# Uav_V2.net
KiCad netlist of a schematic drawn in Altium Designer
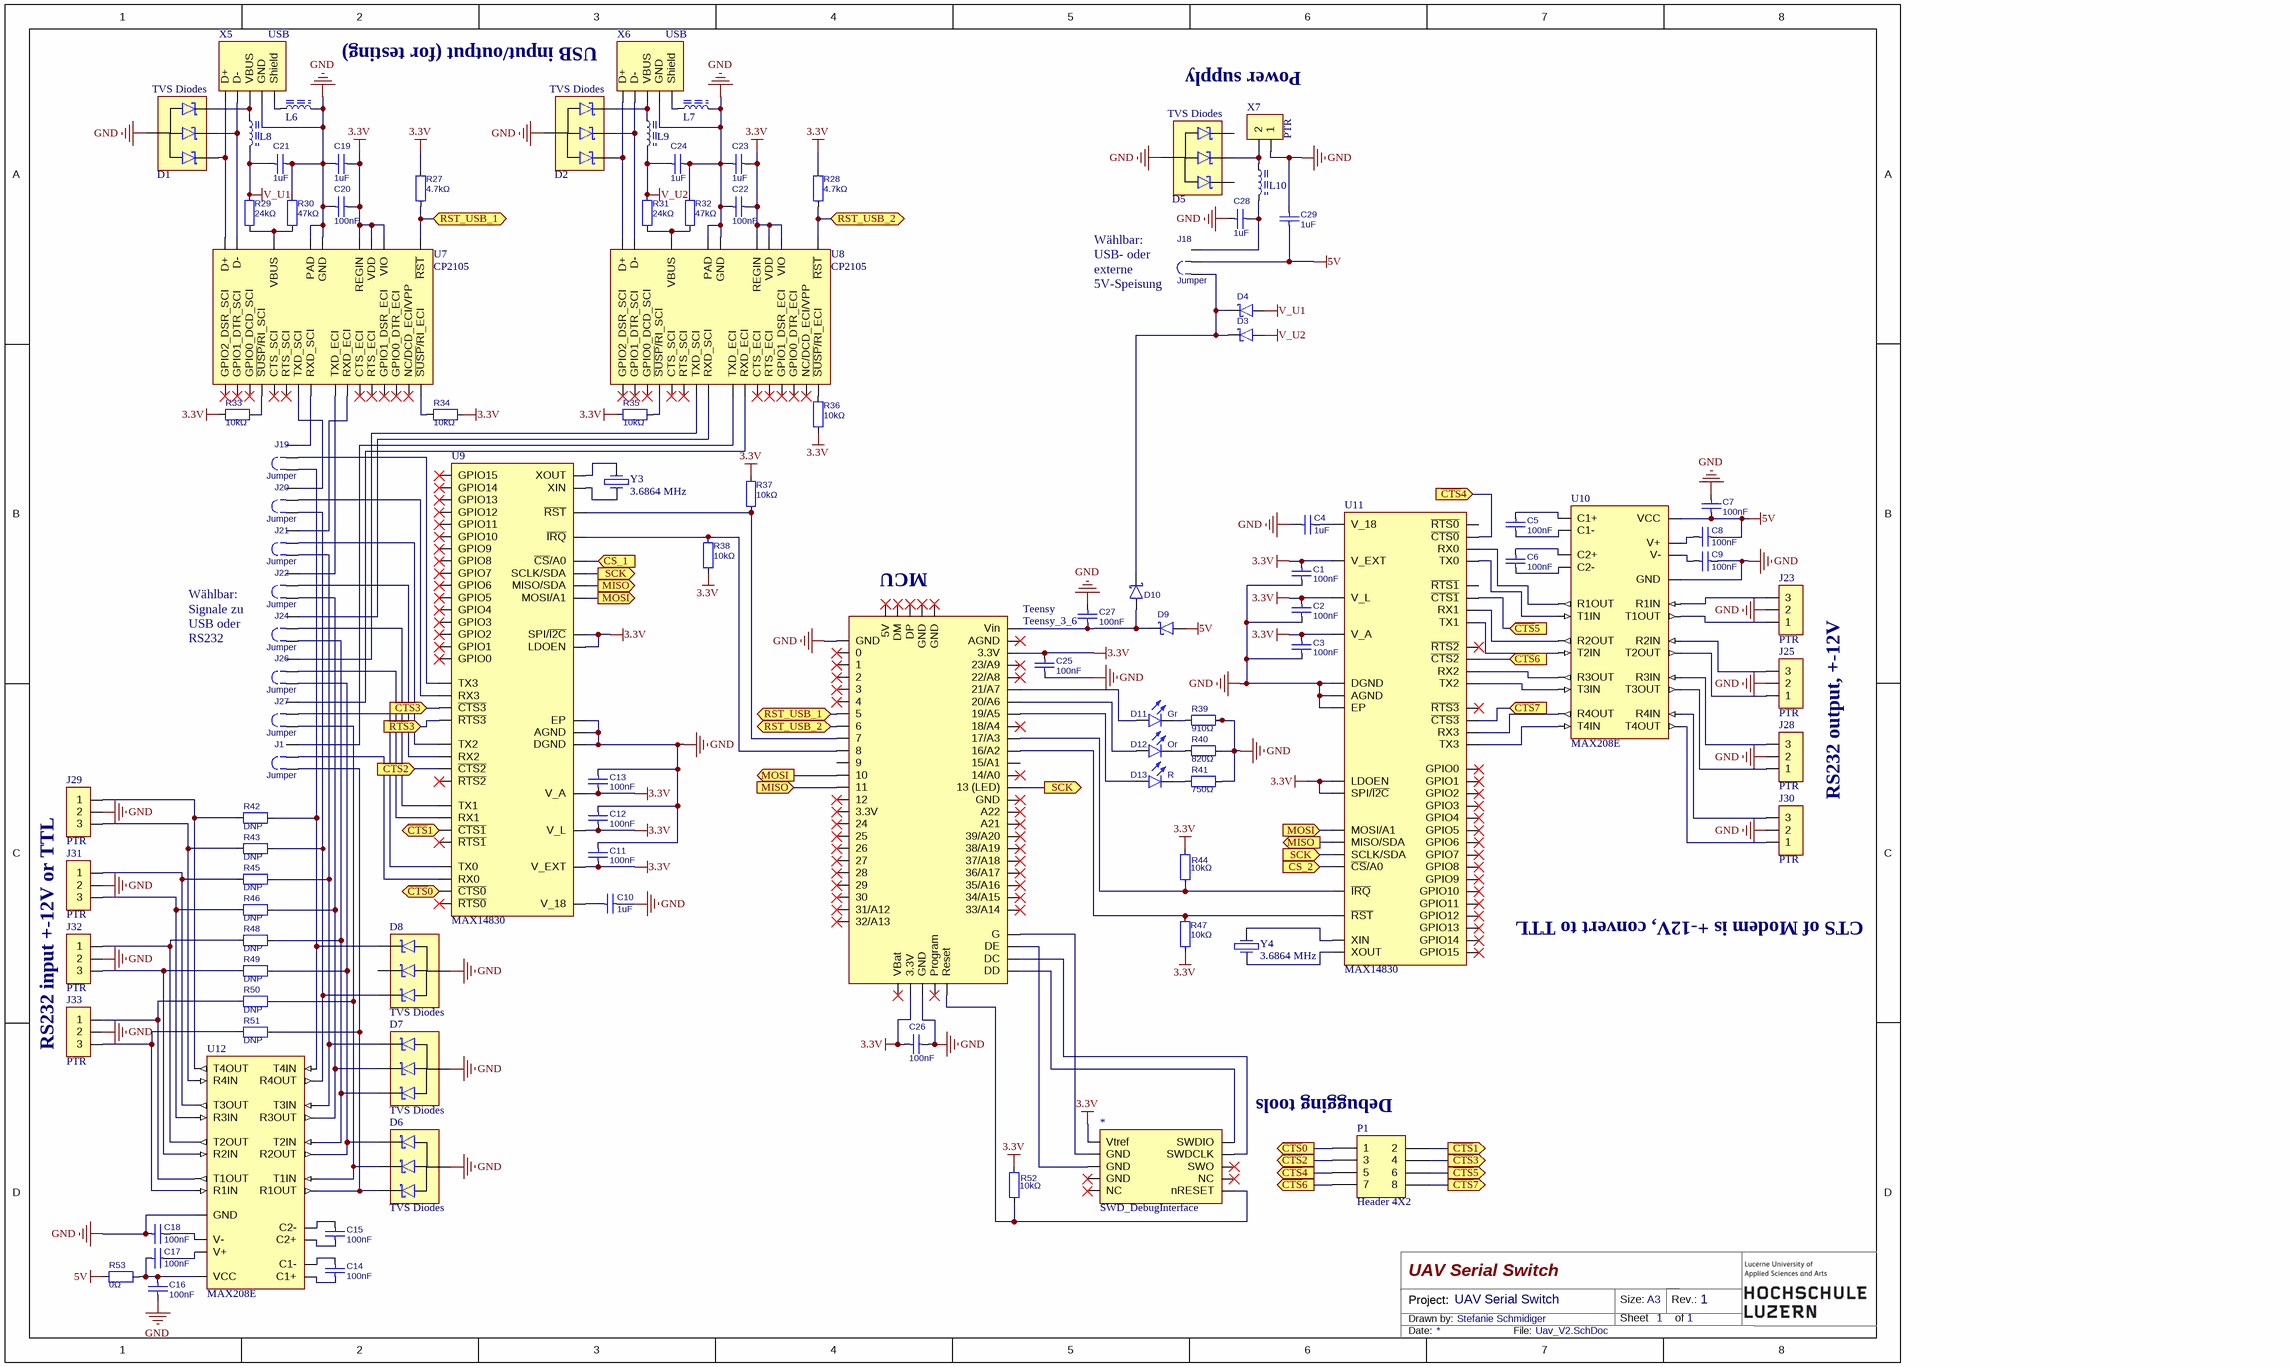
[diagram p0: Uav_V2.SchDoc]

(export (version "E")
  (design (tool "Eeschema 10.0.6"))
  (components
    (comp (ref "*")
      (value "SWD_DebugInterface")
      (footprint "SWD Debug Interface")
      (libsource (lib "UAV") (part "SWD_DebugInterface"))
    )
    (comp (ref "C1")
      (value "100nF")
      (footprint "0603")
      (description "Keramikkondensator 0603")
      (fields (field (name "CHANGED BY") "taalbiss"))
      (libsource (lib "CCE_Database_Libs") (part "C_Normal"))
    )
    (comp (ref "C2")
      (value "100nF")
      (footprint "0603")
      (description "Keramikkondensator 0603")
      (fields (field (name "CHANGED BY") "taalbiss"))
      (libsource (lib "CCE_Database_Libs") (part "C_Normal"))
    )
    (comp (ref "C3")
      (value "100nF")
      (footprint "0603")
      (description "Keramikkondensator 0603")
      (fields (field (name "CHANGED BY") "taalbiss"))
      (libsource (lib "CCE_Database_Libs") (part "C_Normal"))
    )
    (comp (ref "C4")
      (value "1uF")
      (footprint "0603")
      (description "Keramikkondensator 0603")
      (fields (field (name "CHANGED BY") "taalbiss"))
      (libsource (lib "CCE_Database_Libs") (part "C_Normal"))
    )
    (comp (ref "C5")
      (value "100nF")
      (footprint "0603")
      (description "Keramikkondensator 0603")
      (fields (field (name "CHANGED BY") "taalbiss"))
      (libsource (lib "CCE_Database_Libs") (part "C_Normal"))
    )
    (comp (ref "C6")
      (value "100nF")
      (footprint "0603")
      (description "Keramikkondensator 0603")
      (fields (field (name "CHANGED BY") "taalbiss"))
      (libsource (lib "CCE_Database_Libs") (part "C_Normal"))
    )
    (comp (ref "C7")
      (value "100nF")
      (footprint "0603")
      (description "Keramikkondensator 0603")
      (fields (field (name "CHANGED BY") "taalbiss"))
      (libsource (lib "CCE_Database_Libs") (part "C_Normal"))
    )
    (comp (ref "C8")
      (value "100nF")
      (footprint "0603")
      (description "Keramikkondensator 0603")
      (fields (field (name "CHANGED BY") "taalbiss"))
      (libsource (lib "CCE_Database_Libs") (part "C_Normal"))
    )
    (comp (ref "C9")
      (value "100nF")
      (footprint "0603")
      (description "Keramikkondensator 0603")
      (fields (field (name "CHANGED BY") "taalbiss"))
      (libsource (lib "CCE_Database_Libs") (part "C_Normal"))
    )
    (comp (ref "C10")
      (value "1uF")
      (footprint "0603")
      (description "Keramikkondensator 0603")
      (fields (field (name "CHANGED BY") "taalbiss"))
      (libsource (lib "CCE_Database_Libs") (part "C_Normal"))
    )
    (comp (ref "C11")
      (value "100nF")
      (footprint "0603")
      (description "Keramikkondensator 0603")
      (fields (field (name "CHANGED BY") "taalbiss"))
      (libsource (lib "CCE_Database_Libs") (part "C_Normal"))
    )
    (comp (ref "C12")
      (value "100nF")
      (footprint "0603")
      (description "Keramikkondensator 0603")
      (fields (field (name "CHANGED BY") "taalbiss"))
      (libsource (lib "CCE_Database_Libs") (part "C_Normal"))
    )
    (comp (ref "C13")
      (value "100nF")
      (footprint "0603")
      (description "Keramikkondensator 0603")
      (fields (field (name "CHANGED BY") "taalbiss"))
      (libsource (lib "CCE_Database_Libs") (part "C_Normal"))
    )
    (comp (ref "C14")
      (value "100nF")
      (footprint "0603")
      (description "Keramikkondensator 0603")
      (fields (field (name "CHANGED BY") "taalbiss"))
      (libsource (lib "CCE_Database_Libs") (part "C_Normal"))
    )
    (comp (ref "C15")
      (value "100nF")
      (footprint "0603")
      (description "Keramikkondensator 0603")
      (fields (field (name "CHANGED BY") "taalbiss"))
      (libsource (lib "CCE_Database_Libs") (part "C_Normal"))
    )
    (comp (ref "C16")
      (value "100nF")
      (footprint "0603")
      (description "Keramikkondensator 0603")
      (fields (field (name "CHANGED BY") "taalbiss"))
      (libsource (lib "CCE_Database_Libs") (part "C_Normal"))
    )
    (comp (ref "C17")
      (value "100nF")
      (footprint "0603")
      (description "Keramikkondensator 0603")
      (fields (field (name "CHANGED BY") "taalbiss"))
      (libsource (lib "CCE_Database_Libs") (part "C_Normal"))
    )
    (comp (ref "C18")
      (value "100nF")
      (footprint "0603")
      (description "Keramikkondensator 0603")
      (fields (field (name "CHANGED BY") "taalbiss"))
      (libsource (lib "CCE_Database_Libs") (part "C_Normal"))
    )
    (comp (ref "C19")
      (value "1uF")
      (footprint "0603")
      (description "Keramikkondensator 0603")
      (fields (field (name "CHANGED BY") "taalbiss"))
      (libsource (lib "CCE_Database_Libs") (part "C_Normal"))
    )
    (comp (ref "C20")
      (value "100nF")
      (footprint "0603")
      (description "Keramikkondensator 0603")
      (fields (field (name "CHANGED BY") "taalbiss"))
      (libsource (lib "CCE_Database_Libs") (part "C_Normal"))
    )
    (comp (ref "C21")
      (value "1uF")
      (footprint "0603")
      (description "Keramikkondensator 0603")
      (fields (field (name "CHANGED BY") "taalbiss"))
      (libsource (lib "CCE_Database_Libs") (part "C_Normal"))
    )
    (comp (ref "C22")
      (value "100nF")
      (footprint "0603")
      (description "Keramikkondensator 0603")
      (fields (field (name "CHANGED BY") "taalbiss"))
      (libsource (lib "CCE_Database_Libs") (part "C_Normal"))
    )
    (comp (ref "C23")
      (value "1uF")
      (footprint "0603")
      (description "Keramikkondensator 0603")
      (fields (field (name "CHANGED BY") "taalbiss"))
      (libsource (lib "CCE_Database_Libs") (part "C_Normal"))
    )
    (comp (ref "C24")
      (value "1uF")
      (footprint "0603")
      (description "Keramikkondensator 0603")
      (fields (field (name "CHANGED BY") "taalbiss"))
      (libsource (lib "CCE_Database_Libs") (part "C_Normal"))
    )
    (comp (ref "C25")
      (value "100nF")
      (footprint "0603")
      (description "Keramikkondensator 0603")
      (fields (field (name "CHANGED BY") "taalbiss"))
      (libsource (lib "CCE_Database_Libs") (part "C_Normal"))
    )
    (comp (ref "C26")
      (value "100nF")
      (footprint "0603")
      (description "Keramikkondensator 0603")
      (fields (field (name "CHANGED BY") "taalbiss"))
      (libsource (lib "CCE_Database_Libs") (part "C_Normal"))
    )
    (comp (ref "C27")
      (value "100nF")
      (footprint "0603")
      (description "Keramikkondensator 0603")
      (fields (field (name "CHANGED BY") "taalbiss"))
      (libsource (lib "CCE_Database_Libs") (part "C_Normal"))
    )
    (comp (ref "C28")
      (value "1uF")
      (footprint "0603")
      (description "Keramikkondensator 0603")
      (fields (field (name "CHANGED BY") "taalbiss"))
      (libsource (lib "CCE_Database_Libs") (part "C_Normal"))
    )
    (comp (ref "C29")
      (value "1uF")
      (footprint "0603")
      (description "Keramikkondensator 0603")
      (fields (field (name "CHANGED BY") "taalbiss"))
      (libsource (lib "CCE_Database_Libs") (part "C_Normal"))
    )
    (comp (ref "D1")
      (value "TVS Diodes")
      (footprint "UAV:SOT-143-4")
      (libsource (lib "UAV") (part "TVS_Diode_3fach"))
    )
    (comp (ref "D2")
      (value "TVS Diodes")
      (footprint "UAV:SOT-143-4")
      (libsource (lib "UAV") (part "TVS_Diode_3fach"))
    )
    (comp (ref "D3")
      (value "?")
      (footprint "SOD_123")
      (description "Schottky Diode SOD-123")
      (fields (field (name "CHANGED BY") "taalbiss"))
      (libsource (lib "CCE_Database_Libs") (part "Diode_Schottky"))
    )
    (comp (ref "D4")
      (value "?")
      (footprint "SOD_123")
      (description "Schottky Diode SOD-123")
      (fields (field (name "CHANGED BY") "taalbiss"))
      (libsource (lib "CCE_Database_Libs") (part "Diode_Schottky"))
    )
    (comp (ref "D5")
      (value "TVS Diodes")
      (footprint "UAV:SOT-143-4")
      (libsource (lib "UAV") (part "TVS_Diode_3fach"))
    )
    (comp (ref "D6")
      (value "TVS Diodes")
      (footprint "UAV:SOT-143-4")
      (libsource (lib "") (part "TVS_Diode_3fach_1"))
    )
    (comp (ref "D7")
      (value "TVS Diodes")
      (footprint "UAV:SOT-143-4")
      (libsource (lib "") (part "TVS_Diode_3fach_1"))
    )
    (comp (ref "D8")
      (value "TVS Diodes")
      (footprint "UAV:SOT-143-4")
      (libsource (lib "") (part "TVS_Diode_3fach_1"))
    )
    (comp (ref "D9")
      (value "?")
      (footprint "SOD_123")
      (description "Schottky Diode SOD-123")
      (fields (field (name "CHANGED BY") "taalbiss"))
      (libsource (lib "CCE_Database_Libs") (part "Diode_Schottky"))
    )
    (comp (ref "D10")
      (value "?")
      (footprint "SOD_123")
      (description "Schottky Diode SOD-123")
      (fields (field (name "CHANGED BY") "taalbiss"))
      (libsource (lib "CCE_Database_Libs") (part "Diode_Schottky"))
    )
    (comp (ref "D11")
      (value "Gr")
      (footprint "0603D")
      (description "LED SMD 0603")
      (fields (field (name "CHANGED BY") "taalbiss"))
      (libsource (lib "CCE_Database_Libs") (part "LED"))
    )
    (comp (ref "D12")
      (value "Or")
      (footprint "0603D")
      (description "LED SMD 0603")
      (fields (field (name "CHANGED BY") "taalbiss"))
      (libsource (lib "CCE_Database_Libs") (part "LED"))
    )
    (comp (ref "D13")
      (value "R")
      (footprint "0603D")
      (description "LED SMD 0603")
      (fields (field (name "CHANGED BY") "taalbiss"))
      (libsource (lib "CCE_Database_Libs") (part "LED"))
    )
    (comp (ref "J1")
      (value "Jumper")
      (footprint "HDR1X3")
      (description "Jumper THT 2.54mm 1x3")
      (fields (field (name "CHANGED BY") "taalbiss"))
      (libsource (lib "CCE_Database_Libs") (part "Jumper_1x3"))
    )
    (comp (ref "J18")
      (value "Jumper")
      (footprint "HDR1X3")
      (description "Jumper THT 2.54mm 1x3")
      (fields (field (name "CHANGED BY") "taalbiss"))
      (libsource (lib "CCE_Database_Libs") (part "Jumper_1x3"))
    )
    (comp (ref "J19")
      (value "Jumper")
      (footprint "HDR1X3")
      (description "Jumper THT 2.54mm 1x3")
      (fields (field (name "CHANGED BY") "taalbiss"))
      (libsource (lib "CCE_Database_Libs") (part "Jumper_1x3"))
    )
    (comp (ref "J20")
      (value "Jumper")
      (footprint "HDR1X3")
      (description "Jumper THT 2.54mm 1x3")
      (fields (field (name "CHANGED BY") "taalbiss"))
      (libsource (lib "CCE_Database_Libs") (part "Jumper_1x3"))
    )
    (comp (ref "J21")
      (value "Jumper")
      (footprint "HDR1X3")
      (description "Jumper THT 2.54mm 1x3")
      (fields (field (name "CHANGED BY") "taalbiss"))
      (libsource (lib "CCE_Database_Libs") (part "Jumper_1x3"))
    )
    (comp (ref "J22")
      (value "Jumper")
      (footprint "HDR1X3")
      (description "Jumper THT 2.54mm 1x3")
      (fields (field (name "CHANGED BY") "taalbiss"))
      (libsource (lib "CCE_Database_Libs") (part "Jumper_1x3"))
    )
    (comp (ref "J23") (value "PTR") (footprint "PTR_1X3") (libsource (lib "") (part "Header_1x3_1")))
    (comp (ref "J24")
      (value "Jumper")
      (footprint "HDR1X3")
      (description "Jumper THT 2.54mm 1x3")
      (fields (field (name "CHANGED BY") "taalbiss"))
      (libsource (lib "CCE_Database_Libs") (part "Jumper_1x3"))
    )
    (comp (ref "J25") (value "PTR") (footprint "PTR_1X3") (libsource (lib "") (part "Header_1x3_1")))
    (comp (ref "J26")
      (value "Jumper")
      (footprint "HDR1X3")
      (description "Jumper THT 2.54mm 1x3")
      (fields (field (name "CHANGED BY") "taalbiss"))
      (libsource (lib "CCE_Database_Libs") (part "Jumper_1x3"))
    )
    (comp (ref "J27")
      (value "Jumper")
      (footprint "HDR1X3")
      (description "Jumper THT 2.54mm 1x3")
      (fields (field (name "CHANGED BY") "taalbiss"))
      (libsource (lib "CCE_Database_Libs") (part "Jumper_1x3"))
    )
    (comp (ref "J28") (value "PTR") (footprint "PTR_1X3") (libsource (lib "") (part "Header_1x3_1")))
    (comp (ref "J29") (value "PTR") (footprint "PTR_1X3") (libsource (lib "UAV") (part "Header_1x3")))
    (comp (ref "J30") (value "PTR") (footprint "PTR_1X3") (libsource (lib "") (part "Header_1x3_1")))
    (comp (ref "J31") (value "PTR") (footprint "PTR_1X3") (libsource (lib "UAV") (part "Header_1x3")))
    (comp (ref "J32") (value "PTR") (footprint "PTR_1X3") (libsource (lib "UAV") (part "Header_1x3")))
    (comp (ref "J33") (value "PTR") (footprint "PTR_1X3") (libsource (lib "UAV") (part "Header_1x3")))
    (comp (ref "L6")
      (value "MPZ1608S601A")
      (footprint "0603")
      (description "Ferrit 0603")
      (fields (field (name "CHANGED BY") "taalbiss"))
      (libsource (lib "CCE_Database_Libs") (part "L_Ferrite"))
    )
    (comp (ref "L7")
      (value "MPZ1608S601A")
      (footprint "0603")
      (description "Ferrit 0603")
      (fields (field (name "CHANGED BY") "taalbiss"))
      (libsource (lib "CCE_Database_Libs") (part "L_Ferrite"))
    )
    (comp (ref "L8")
      (value "MPZ1608S601A")
      (footprint "0603")
      (description "Ferrit 0603")
      (fields (field (name "CHANGED BY") "taalbiss"))
      (libsource (lib "CCE_Database_Libs") (part "L_Ferrite"))
    )
    (comp (ref "L9")
      (value "MPZ1608S601A")
      (footprint "0603")
      (description "Ferrit 0603")
      (fields (field (name "CHANGED BY") "taalbiss"))
      (libsource (lib "CCE_Database_Libs") (part "L_Ferrite"))
    )
    (comp (ref "L10")
      (value "MPZ1608S601A")
      (footprint "0603")
      (description "Ferrit 0603")
      (fields (field (name "CHANGED BY") "taalbiss"))
      (libsource (lib "CCE_Database_Libs") (part "L_Ferrite"))
    )
    (comp (ref "P1")
      (value "Header 4X2")
      (footprint "HDR2X4")
      (description "Header, 4-Pin, Dual row")
      (fields (field (name "PUBLISHER") "Altium Limited"))
      (libsource (lib "Miscellaneous Connectors") (part "Header 4X2"))
    )
    (comp (ref "R27")
      (value "4.7kΩ")
      (footprint "0603")
      (description "Widerstand 0603")
      (fields (field (name "CHANGED BY") "taalbiss"))
      (libsource (lib "") (part "R_Normal_2"))
    )
    (comp (ref "R28")
      (value "4.7kΩ")
      (footprint "0603")
      (description "Widerstand 0603")
      (fields (field (name "CHANGED BY") "taalbiss"))
      (libsource (lib "") (part "R_Normal_2"))
    )
    (comp (ref "R29")
      (value "24kΩ")
      (footprint "0603")
      (description "Widerstand 0603")
      (fields (field (name "CHANGED BY") "taalbiss"))
      (libsource (lib "") (part "R_Normal_1"))
    )
    (comp (ref "R30")
      (value "47kΩ")
      (footprint "0603")
      (description "Widerstand 0603")
      (fields (field (name "CHANGED BY") "taalbiss"))
      (libsource (lib "") (part "R_Normal_1"))
    )
    (comp (ref "R31")
      (value "24kΩ")
      (footprint "0603")
      (description "Widerstand 0603")
      (fields (field (name "CHANGED BY") "taalbiss"))
      (libsource (lib "") (part "R_Normal_1"))
    )
    (comp (ref "R32")
      (value "47kΩ")
      (footprint "0603")
      (description "Widerstand 0603")
      (fields (field (name "CHANGED BY") "taalbiss"))
      (libsource (lib "") (part "R_Normal_1"))
    )
    (comp (ref "R33")
      (value "10kΩ")
      (footprint "0603")
      (description "Widerstand 0603")
      (fields (field (name "CHANGED BY") "taalbiss"))
      (libsource (lib "CCE_Database_Libs") (part "R_Normal"))
    )
    (comp (ref "R34")
      (value "10kΩ")
      (footprint "0603")
      (description "Widerstand 0603")
      (fields (field (name "CHANGED BY") "taalbiss"))
      (libsource (lib "CCE_Database_Libs") (part "R_Normal"))
    )
    (comp (ref "R35")
      (value "10kΩ")
      (footprint "0603")
      (description "Widerstand 0603")
      (fields (field (name "CHANGED BY") "taalbiss"))
      (libsource (lib "CCE_Database_Libs") (part "R_Normal"))
    )
    (comp (ref "R36")
      (value "10kΩ")
      (footprint "0603")
      (description "Widerstand 0603")
      (fields (field (name "CHANGED BY") "taalbiss"))
      (libsource (lib "") (part "R_Normal_2"))
    )
    (comp (ref "R37")
      (value "10kΩ")
      (footprint "0603")
      (description "Widerstand 0603")
      (fields (field (name "CHANGED BY") "taalbiss"))
      (libsource (lib "") (part "R_Normal_2"))
    )
    (comp (ref "R38")
      (value "10kΩ")
      (footprint "0603")
      (description "Widerstand 0603")
      (fields (field (name "CHANGED BY") "taalbiss"))
      (libsource (lib "") (part "R_Normal_2"))
    )
    (comp (ref "R39")
      (value "910Ω")
      (footprint "0603")
      (description "Widerstand 0603")
      (fields (field (name "CHANGED BY") "taalbiss"))
      (libsource (lib "CCE_Database_Libs") (part "R_Normal"))
    )
    (comp (ref "R40")
      (value "820Ω")
      (footprint "0603")
      (description "Widerstand 0603")
      (fields (field (name "CHANGED BY") "taalbiss"))
      (libsource (lib "CCE_Database_Libs") (part "R_Normal"))
    )
    (comp (ref "R41")
      (value "750Ω")
      (footprint "0603")
      (description "Widerstand 0603")
      (fields (field (name "CHANGED BY") "taalbiss"))
      (libsource (lib "CCE_Database_Libs") (part "R_Normal"))
    )
    (comp (ref "R42")
      (value "DNP")
      (footprint "0603")
      (description "Widerstand 0603")
      (fields (field (name "CHANGED BY") "taalbiss"))
      (libsource (lib "CCE_Database_Libs") (part "R_Normal"))
    )
    (comp (ref "R43")
      (value "DNP")
      (footprint "0603")
      (description "Widerstand 0603")
      (fields (field (name "CHANGED BY") "taalbiss"))
      (libsource (lib "CCE_Database_Libs") (part "R_Normal"))
    )
    (comp (ref "R44")
      (value "10kΩ")
      (footprint "0603")
      (description "Widerstand 0603")
      (fields (field (name "CHANGED BY") "taalbiss"))
      (libsource (lib "") (part "R_Normal_2"))
    )
    (comp (ref "R45")
      (value "DNP")
      (footprint "0603")
      (description "Widerstand 0603")
      (fields (field (name "CHANGED BY") "taalbiss"))
      (libsource (lib "CCE_Database_Libs") (part "R_Normal"))
    )
    (comp (ref "R46")
      (value "DNP")
      (footprint "0603")
      (description "Widerstand 0603")
      (fields (field (name "CHANGED BY") "taalbiss"))
      (libsource (lib "CCE_Database_Libs") (part "R_Normal"))
    )
    (comp (ref "R47")
      (value "10kΩ")
      (footprint "0603")
      (description "Widerstand 0603")
      (fields (field (name "CHANGED BY") "taalbiss"))
      (libsource (lib "") (part "R_Normal_2"))
    )
    (comp (ref "R48")
      (value "DNP")
      (footprint "0603")
      (description "Widerstand 0603")
      (fields (field (name "CHANGED BY") "taalbiss"))
      (libsource (lib "CCE_Database_Libs") (part "R_Normal"))
    )
    (comp (ref "R49")
      (value "DNP")
      (footprint "0603")
      (description "Widerstand 0603")
      (fields (field (name "CHANGED BY") "taalbiss"))
      (libsource (lib "CCE_Database_Libs") (part "R_Normal"))
    )
    (comp (ref "R50")
      (value "DNP")
      (footprint "0603")
      (description "Widerstand 0603")
      (fields (field (name "CHANGED BY") "taalbiss"))
      (libsource (lib "CCE_Database_Libs") (part "R_Normal"))
    )
    (comp (ref "R51")
      (value "DNP")
      (footprint "0603")
      (description "Widerstand 0603")
      (fields (field (name "CHANGED BY") "taalbiss"))
      (libsource (lib "CCE_Database_Libs") (part "R_Normal"))
    )
    (comp (ref "R52")
      (value "10kΩ")
      (footprint "0603")
      (description "Widerstand 0603")
      (fields (field (name "CHANGED BY") "taalbiss"))
      (libsource (lib "") (part "R_Normal_2"))
    )
    (comp (ref "R53")
      (value "0Ω")
      (footprint "0603")
      (description "Widerstand 0603")
      (fields (field (name "CHANGED BY") "taalbiss"))
      (libsource (lib "CCE_Database_Libs") (part "R_Normal"))
    )
    (comp (ref "Teensy") (value "Teensy_3_6") (libsource (lib "UAV") (part "Teensy_3_6")))
    (comp (ref "U7") (value "CP2105") (footprint "UAV:QFN24") (libsource (lib "UAV") (part "CP2105")))
    (comp (ref "U8") (value "CP2105") (footprint "UAV:QFN24") (libsource (lib "UAV") (part "CP2105")))
    (comp (ref "U9") (value "MAX14830") (footprint "UAV:TQFN48") (libsource (lib "UAV") (part "MAX14830")))
    (comp (ref "U10") (value "MAX208E") (footprint "UAV:SSOP24") (libsource (lib "") (part "MAX208E_1")))
    (comp (ref "U11") (value "MAX14830") (footprint "UAV:TQFN48") (libsource (lib "") (part "MAX14830_1")))
    (comp (ref "U12") (value "MAX208E") (footprint "UAV:SSOP24") (libsource (lib "UAV") (part "MAX208E")))
    (comp (ref "X5") (value "USB") (footprint "ZX63-B-5PA(30)") (libsource (lib "UAV") (part "USB")))
    (comp (ref "X6") (value "USB") (footprint "ZX63-B-5PA(30)") (libsource (lib "UAV") (part "USB")))
    (comp (ref "X7") (value "PTR") (footprint "UAV:PTR_1X2") (libsource (lib "UAV") (part "Header_1x2")))
    (comp (ref "Y3")
      (value "3.6864 MHz")
      (footprint "UAV:Crystal_10x4_5mm")
      (libsource (lib "UAV") (part "Crystal_3_6864_MHz"))
    )
    (comp (ref "Y4")
      (value "3.6864 MHz")
      (footprint "UAV:Crystal_10x4_5mm")
      (libsource (lib "UAV") (part "Crystal_3_6864_MHz"))
    )
  )
  (nets
    (net (code "1") (name "/CS_1") (class "Default")
      (node (ref "U9") (pin "5") (pinfunction "~{CS}/A0_5") (pintype "passive"))
    )
    (net (code "2") (name "/CS_2") (class "Default")
      (node (ref "U11") (pin "5") (pinfunction "~{CS}/A0_5") (pintype "passive"))
    )
    (net (code "3") (name "/MISO") (class "Default")
      (node (ref "Teensy") (pin "11") (pinfunction "11_11") (pintype "passive"))
      (node (ref "U11") (pin "3") (pinfunction "MISO/SDA_3") (pintype "passive"))
      (node (ref "U9") (pin "3") (pinfunction "MISO/SDA_3") (pintype "passive"))
    )
    (net (code "4") (name "/MOSI") (class "Default")
      (node (ref "Teensy") (pin "10") (pinfunction "10_10") (pintype "passive"))
      (node (ref "U11") (pin "6") (pinfunction "MOSI/A1_6") (pintype "passive"))
      (node (ref "U9") (pin "6") (pinfunction "MOSI/A1_6") (pintype "passive"))
    )
    (net (code "5") (name "/RST_USB_1") (class "Default")
      (node (ref "R27") (pin "1") (pinfunction "1_1") (pintype "passive"))
      (node (ref "Teensy") (pin "5") (pinfunction "5_5") (pintype "passive"))
      (node (ref "U7") (pin "9") (pinfunction "~{RST}_9") (pintype "passive"))
    )
    (net (code "6") (name "/RST_USB_2") (class "Default")
      (node (ref "R28") (pin "1") (pinfunction "1_1") (pintype "passive"))
      (node (ref "Teensy") (pin "6") (pinfunction "6_6") (pintype "passive"))
      (node (ref "U8") (pin "9") (pinfunction "~{RST}_9") (pintype "passive"))
    )
    (net (code "7") (name "/SCK") (class "Default")
      (node (ref "Teensy") (pin "13") (pinfunction "13_(LED)_13") (pintype "passive"))
      (node (ref "U11") (pin "4") (pinfunction "SCLK/SDA_4") (pintype "passive"))
      (node (ref "U9") (pin "4") (pinfunction "SCLK/SDA_4") (pintype "passive"))
    )
    (net (code "8") (name "/~{CTS}0") (class "Default")
      (node (ref "P1") (pin "1") (pinfunction "1_1") (pintype "passive"))
      (node (ref "U9") (pin "16") (pinfunction "~{CTS0}_16") (pintype "passive"))
    )
    (net (code "9") (name "/~{CTS}1") (class "Default")
      (node (ref "P1") (pin "2") (pinfunction "2_2") (pintype "passive"))
      (node (ref "U9") (pin "24") (pinfunction "~{CTS1}_24") (pintype "passive"))
    )
    (net (code "10") (name "/~{CTS}2") (class "Default")
      (node (ref "P1") (pin "3") (pinfunction "3_3") (pintype "passive"))
      (node (ref "U9") (pin "32") (pinfunction "~{CTS2}_32") (pintype "passive"))
    )
    (net (code "11") (name "/~{CTS}3") (class "Default")
      (node (ref "P1") (pin "4") (pinfunction "4_4") (pintype "passive"))
      (node (ref "U9") (pin "40") (pinfunction "~{CTS3}_40") (pintype "passive"))
    )
    (net (code "12") (name "/~{CTS}4") (class "Default")
      (node (ref "P1") (pin "5") (pinfunction "5_5") (pintype "passive"))
      (node (ref "U11") (pin "16") (pinfunction "~{CTS0}_16") (pintype "passive"))
    )
    (net (code "13") (name "/~{CTS}5") (class "Default")
      (node (ref "P1") (pin "6") (pinfunction "6_6") (pintype "passive"))
      (node (ref "U11") (pin "24") (pinfunction "~{CTS1}_24") (pintype "passive"))
    )
    (net (code "14") (name "/~{CTS}6") (class "Default")
      (node (ref "P1") (pin "7") (pinfunction "7_7") (pintype "passive"))
      (node (ref "U11") (pin "32") (pinfunction "~{CTS2}_32") (pintype "passive"))
    )
    (net (code "15") (name "/~{CTS}7") (class "Default")
      (node (ref "P1") (pin "8") (pinfunction "8_8") (pintype "passive"))
      (node (ref "U11") (pin "40") (pinfunction "~{CTS3}_40") (pintype "passive"))
    )
    (net (code "16") (name "/~{RTS}3") (class "Default")
      (node (ref "U9") (pin "39") (pinfunction "~{RTS3}_39") (pintype "passive"))
    )
    (net (code "17") (name "3.3V") (class "Default")
      (node (ref "*") (pin "1") (pinfunction "Vtref_1") (pintype "passive"))
      (node (ref "C1") (pin "2") (pinfunction "2_2") (pintype "passive"))
      (node (ref "C11") (pin "2") (pinfunction "2_2") (pintype "passive"))
      (node (ref "C12") (pin "2") (pinfunction "2_2") (pintype "passive"))
      (node (ref "C13") (pin "2") (pinfunction "2_2") (pintype "passive"))
      (node (ref "C19") (pin "1") (pinfunction "1_1") (pintype "passive"))
      (node (ref "C2") (pin "2") (pinfunction "2_2") (pintype "passive"))
      (node (ref "C20") (pin "1") (pinfunction "1_1") (pintype "passive"))
      (node (ref "C22") (pin "1") (pinfunction "1_1") (pintype "passive"))
      (node (ref "C23") (pin "1") (pinfunction "1_1") (pintype "passive"))
      (node (ref "C25") (pin "1") (pinfunction "1_1") (pintype "passive"))
      (node (ref "C26") (pin "1") (pinfunction "1_1") (pintype "passive"))
      (node (ref "C3") (pin "2") (pinfunction "2_2") (pintype "passive"))
      (node (ref "R27") (pin "2") (pinfunction "2_2") (pintype "passive"))
      (node (ref "R28") (pin "2") (pinfunction "2_2") (pintype "passive"))
      (node (ref "R33") (pin "2") (pinfunction "2_2") (pintype "passive"))
      (node (ref "R34") (pin "1") (pinfunction "1_1") (pintype "passive"))
      (node (ref "R35") (pin "2") (pinfunction "2_2") (pintype "passive"))
      (node (ref "R36") (pin "1") (pinfunction "1_1") (pintype "passive"))
      (node (ref "R37") (pin "2") (pinfunction "2_2") (pintype "passive"))
      (node (ref "R38") (pin "1") (pinfunction "1_1") (pintype "passive"))
      (node (ref "R44") (pin "2") (pinfunction "2_2") (pintype "passive"))
      (node (ref "R47") (pin "1") (pinfunction "1_1") (pintype "passive"))
      (node (ref "R52") (pin "2") (pinfunction "2_2") (pintype "passive"))
      (node (ref "Teensy") (pin "3.3V_1") (pinfunction "3.3V_3.3V_1") (pintype "passive"))
      (node (ref "Teensy") (pin "3.3V_2") (pinfunction "3.3V_3.3V_2") (pintype "passive"))
      (node (ref "U11") (pin "1") (pinfunction "SPI/~{I2C}_1") (pintype "passive"))
      (node (ref "U11") (pin "2") (pinfunction "LDOEN_2") (pintype "passive"))
      (node (ref "U11") (pin "43") (pinfunction "V_EXT_43") (pintype "passive"))
      (node (ref "U11") (pin "47") (pinfunction "V_A_47") (pintype "passive"))
      (node (ref "U11") (pin "9") (pinfunction "V_L_9") (pintype "passive"))
      (node (ref "U7") (pin "5") (pinfunction "VIO_5") (pintype "passive"))
      (node (ref "U7") (pin "6") (pinfunction "VDD_6") (pintype "passive"))
      (node (ref "U7") (pin "7") (pinfunction "REGIN_7") (pintype "passive"))
      (node (ref "U8") (pin "5") (pinfunction "VIO_5") (pintype "passive"))
      (node (ref "U8") (pin "6") (pinfunction "VDD_6") (pintype "passive"))
      (node (ref "U8") (pin "7") (pinfunction "REGIN_7") (pintype "passive"))
      (node (ref "U9") (pin "1") (pinfunction "SPI/~{I2C}_1") (pintype "passive"))
      (node (ref "U9") (pin "2") (pinfunction "LDOEN_2") (pintype "passive"))
      (node (ref "U9") (pin "43") (pinfunction "V_EXT_43") (pintype "passive"))
      (node (ref "U9") (pin "47") (pinfunction "V_A_47") (pintype "passive"))
      (node (ref "U9") (pin "9") (pinfunction "V_L_9") (pintype "passive"))
    )
    (net (code "18") (name "5V") (class "Default")
      (node (ref "C29") (pin "1") (pinfunction "1_1") (pintype "passive"))
      (node (ref "C7") (pin "1") (pinfunction "1_1") (pintype "passive"))
      (node (ref "C8") (pin "1") (pinfunction "1_1") (pintype "passive"))
      (node (ref "D9") (pin "1") (pinfunction "A_1") (pintype "passive"))
      (node (ref "J18") (pin "2") (pinfunction "2_2") (pintype "passive"))
      (node (ref "R53") (pin "2") (pinfunction "2_2") (pintype "passive"))
      (node (ref "U10") (pin "9") (pinfunction "VCC_9") (pintype "passive"))
    )
    (net (code "19") (name "GND") (class "Default")
      (node (ref "C1") (pin "1") (pinfunction "1_1") (pintype "passive"))
      (node (ref "C10") (pin "1") (pinfunction "1_1") (pintype "passive"))
      (node (ref "C11") (pin "1") (pinfunction "1_1") (pintype "passive"))
      (node (ref "C12") (pin "1") (pinfunction "1_1") (pintype "passive"))
      (node (ref "C13") (pin "1") (pinfunction "1_1") (pintype "passive"))
      (node (ref "C16") (pin "2") (pinfunction "2_2") (pintype "passive"))
      (node (ref "C18") (pin "1") (pinfunction "1_1") (pintype "passive"))
      (node (ref "C19") (pin "2") (pinfunction "2_2") (pintype "passive"))
      (node (ref "C2") (pin "1") (pinfunction "1_1") (pintype "passive"))
      (node (ref "C20") (pin "2") (pinfunction "2_2") (pintype "passive"))
      (node (ref "C21") (pin "1") (pinfunction "1_1") (pintype "passive"))
      (node (ref "C22") (pin "2") (pinfunction "2_2") (pintype "passive"))
      (node (ref "C23") (pin "2") (pinfunction "2_2") (pintype "passive"))
      (node (ref "C24") (pin "1") (pinfunction "1_1") (pintype "passive"))
      (node (ref "C25") (pin "2") (pinfunction "2_2") (pintype "passive"))
      (node (ref "C26") (pin "2") (pinfunction "2_2") (pintype "passive"))
      (node (ref "C27") (pin "1") (pinfunction "1_1") (pintype "passive"))
      (node (ref "C28") (pin "2") (pinfunction "2_2") (pintype "passive"))
      (node (ref "C29") (pin "2") (pinfunction "2_2") (pintype "passive"))
      (node (ref "C3") (pin "1") (pinfunction "1_1") (pintype "passive"))
      (node (ref "C4") (pin "1") (pinfunction "1_1") (pintype "passive"))
      (node (ref "C7") (pin "2") (pinfunction "2_2") (pintype "passive"))
      (node (ref "C9") (pin "1") (pinfunction "1_1") (pintype "passive"))
      (node (ref "D1") (pin "1") (pinfunction "CA_1") (pintype "passive"))
      (node (ref "D2") (pin "1") (pinfunction "CA_1") (pintype "passive"))
      (node (ref "D5") (pin "1") (pinfunction "CA_1") (pintype "passive"))
      (node (ref "D6") (pin "1") (pinfunction "CA_1") (pintype "passive"))
      (node (ref "D7") (pin "1") (pinfunction "CA_1") (pintype "passive"))
      (node (ref "D8") (pin "1") (pinfunction "CA_1") (pintype "passive"))
      (node (ref "J23") (pin "2") (pinfunction "2_2") (pintype "passive"))
      (node (ref "J25") (pin "2") (pinfunction "2_2") (pintype "passive"))
      (node (ref "J28") (pin "2") (pinfunction "2_2") (pintype "passive"))
      (node (ref "J29") (pin "2") (pinfunction "2_2") (pintype "passive"))
      (node (ref "J30") (pin "2") (pinfunction "2_2") (pintype "passive"))
      (node (ref "J31") (pin "2") (pinfunction "2_2") (pintype "passive"))
      (node (ref "J32") (pin "2") (pinfunction "2_2") (pintype "passive"))
      (node (ref "J33") (pin "2") (pinfunction "2_2") (pintype "passive"))
      (node (ref "L6") (pin "2") (pinfunction "2_2") (pintype "passive"))
      (node (ref "L7") (pin "2") (pinfunction "2_2") (pintype "passive"))
      (node (ref "R30") (pin "1") (pinfunction "1_1") (pintype "passive"))
      (node (ref "R32") (pin "1") (pinfunction "1_1") (pintype "passive"))
      (node (ref "R39") (pin "1") (pinfunction "1_1") (pintype "passive"))
      (node (ref "R40") (pin "1") (pinfunction "1_1") (pintype "passive"))
      (node (ref "R41") (pin "1") (pinfunction "1_1") (pintype "passive"))
      (node (ref "Teensy") (pin "GND_1") (pinfunction "GND_GND_1") (pintype "passive"))
      (node (ref "Teensy") (pin "GND_2") (pinfunction "GND_GND_2") (pintype "passive"))
      (node (ref "U10") (pin "8") (pinfunction "GND_8") (pintype "passive"))
      (node (ref "U11") (pin "10") (pinfunction "DGND_10") (pintype "passive"))
      (node (ref "U11") (pin "46") (pinfunction "AGND_46") (pintype "passive"))
      (node (ref "U11") (pin "49") (pinfunction "EP_49") (pintype "passive"))
      (node (ref "U12") (pin "8") (pinfunction "GND_8") (pintype "passive"))
      (node (ref "U7") (pin "2") (pinfunction "GND_2") (pintype "passive"))
      (node (ref "U7") (pin "25") (pinfunction "PAD_25") (pintype "passive"))
      (node (ref "U8") (pin "2") (pinfunction "GND_2") (pintype "passive"))
      (node (ref "U8") (pin "25") (pinfunction "PAD_25") (pintype "passive"))
      (node (ref "U9") (pin "10") (pinfunction "DGND_10") (pintype "passive"))
      (node (ref "U9") (pin "46") (pinfunction "AGND_46") (pintype "passive"))
      (node (ref "U9") (pin "49") (pinfunction "EP_49") (pintype "passive"))
      (node (ref "X5") (pin "4") (pinfunction "GND_4") (pintype "passive"))
      (node (ref "X6") (pin "4") (pinfunction "GND_4") (pintype "passive"))
      (node (ref "X7") (pin "1") (pinfunction "1_1") (pintype "passive"))
    )
    (net (code "20") (name "Net-(*-GND-Pad7)") (class "Default")
      (node (ref "*") (pin "7") (pinfunction "GND_7") (pintype "passive"))
      (node (ref "Teensy") (pin "DE") (pinfunction "DE_DE") (pintype "passive"))
    )
    (net (code "21") (name "Net-(*-SWDCLK)") (class "Default")
      (node (ref "*") (pin "4") (pinfunction "SWDCLK_4") (pintype "passive"))
      (node (ref "Teensy") (pin "DC") (pinfunction "DC_DC") (pintype "passive"))
    )
    (net (code "22") (name "Net-(*-SWDIO)") (class "Default")
      (node (ref "*") (pin "2") (pinfunction "SWDIO_2") (pintype "passive"))
      (node (ref "Teensy") (pin "DD") (pinfunction "DD_DD") (pintype "passive"))
    )
    (net (code "23") (name "Net-(*-nRESET)") (class "Default")
      (node (ref "*") (pin "10") (pinfunction "nRESET_10") (pintype "passive"))
      (node (ref "R52") (pin "1") (pinfunction "1_1") (pintype "passive"))
      (node (ref "Teensy") (pin "Reset") (pinfunction "Reset_Reset") (pintype "passive"))
    )
    (net (code "24") (name "Net-(C28-Pad1)") (class "Default")
      (node (ref "C28") (pin "1") (pinfunction "1_1") (pintype "passive"))
      (node (ref "J18") (pin "3") (pinfunction "3_3") (pintype "passive"))
      (node (ref "L10") (pin "2") (pinfunction "2_2") (pintype "passive"))
    )
    (net (code "25") (name "Net-(D1-K1)") (class "Default")
      (node (ref "D1") (pin "2") (pinfunction "K1_2") (pintype "passive"))
      (node (ref "U7") (pin "3") (pinfunction "D+_3") (pintype "passive"))
      (node (ref "X5") (pin "3") (pinfunction "D+_3") (pintype "passive"))
    )
    (net (code "26") (name "Net-(D1-K2)") (class "Default")
      (node (ref "D1") (pin "3") (pinfunction "K2_3") (pintype "passive"))
      (node (ref "U7") (pin "4") (pinfunction "D-_4") (pintype "passive"))
      (node (ref "X5") (pin "2") (pinfunction "D-_2") (pintype "passive"))
    )
    (net (code "27") (name "Net-(D1-K3)") (class "Default")
      (node (ref "D1") (pin "4") (pinfunction "K3_4") (pintype "passive"))
      (node (ref "L8") (pin "1") (pinfunction "1_1") (pintype "passive"))
      (node (ref "X5") (pin "1") (pinfunction "VBUS_1") (pintype "passive"))
    )
    (net (code "28") (name "Net-(D2-K1)") (class "Default")
      (node (ref "D2") (pin "2") (pinfunction "K1_2") (pintype "passive"))
      (node (ref "U8") (pin "3") (pinfunction "D+_3") (pintype "passive"))
      (node (ref "X6") (pin "3") (pinfunction "D+_3") (pintype "passive"))
    )
    (net (code "29") (name "Net-(D2-K2)") (class "Default")
      (node (ref "D2") (pin "3") (pinfunction "K2_3") (pintype "passive"))
      (node (ref "U8") (pin "4") (pinfunction "D-_4") (pintype "passive"))
      (node (ref "X6") (pin "2") (pinfunction "D-_2") (pintype "passive"))
    )
    (net (code "30") (name "Net-(D2-K3)") (class "Default")
      (node (ref "D2") (pin "4") (pinfunction "K3_4") (pintype "passive"))
      (node (ref "L9") (pin "1") (pinfunction "1_1") (pintype "passive"))
      (node (ref "X6") (pin "1") (pinfunction "VBUS_1") (pintype "passive"))
    )
    (net (code "31") (name "Net-(D5-K2)") (class "Default")
      (node (ref "D5") (pin "3") (pinfunction "K2_3") (pintype "passive"))
      (node (ref "L10") (pin "1") (pinfunction "1_1") (pintype "passive"))
      (node (ref "X7") (pin "2") (pinfunction "2_2") (pintype "passive"))
    )
    (net (code "32") (name "Net-(D6-K1)") (class "Default")
      (node (ref "D6") (pin "2") (pinfunction "K1_2") (pintype "passive"))
      (node (ref "J26") (pin "1") (pinfunction "1_1") (pintype "passive"))
      (node (ref "R49") (pin "1") (pinfunction "1_1") (pintype "passive"))
      (node (ref "U12") (pin "4") (pinfunction "R2OUT_4") (pintype "output"))
    )
    (net (code "33") (name "Net-(D6-K2)") (class "Default")
      (node (ref "D6") (pin "3") (pinfunction "K2_3") (pintype "passive"))
      (node (ref "J27") (pin "1") (pinfunction "1_1") (pintype "passive"))
      (node (ref "R50") (pin "1") (pinfunction "1_1") (pintype "passive"))
      (node (ref "U12") (pin "5") (pinfunction "T1IN_5") (pintype "input"))
    )
    (net (code "34") (name "Net-(D6-K3)") (class "Default")
      (node (ref "D6") (pin "4") (pinfunction "K3_4") (pintype "passive"))
      (node (ref "J1") (pin "1") (pinfunction "1_1") (pintype "passive"))
      (node (ref "R51") (pin "1") (pinfunction "1_1") (pintype "passive"))
      (node (ref "U12") (pin "6") (pinfunction "R1OUT_6") (pintype "output"))
    )
    (net (code "35") (name "Net-(D7-K1)") (class "Default")
      (node (ref "D7") (pin "2") (pinfunction "K1_2") (pintype "passive"))
      (node (ref "J21") (pin "1") (pinfunction "1_1") (pintype "passive"))
      (node (ref "R45") (pin "1") (pinfunction "1_1") (pintype "passive"))
      (node (ref "U12") (pin "19") (pinfunction "T3IN_19") (pintype "input"))
    )
    (net (code "36") (name "Net-(D7-K2)") (class "Default")
      (node (ref "D7") (pin "3") (pinfunction "K2_3") (pintype "passive"))
      (node (ref "J22") (pin "1") (pinfunction "1_1") (pintype "passive"))
      (node (ref "R46") (pin "1") (pinfunction "1_1") (pintype "passive"))
      (node (ref "U12") (pin "22") (pinfunction "R3OUT_22") (pintype "output"))
    )
    (net (code "37") (name "Net-(D7-K3)") (class "Default")
      (node (ref "D7") (pin "4") (pinfunction "K3_4") (pintype "passive"))
      (node (ref "J24") (pin "1") (pinfunction "1_1") (pintype "passive"))
      (node (ref "R48") (pin "1") (pinfunction "1_1") (pintype "passive"))
      (node (ref "U12") (pin "18") (pinfunction "T2IN_18") (pintype "input"))
    )
    (net (code "38") (name "Net-(D8-K1)") (class "Default")
      (node (ref "D8") (pin "2") (pinfunction "K1_2") (pintype "passive"))
      (node (ref "J19") (pin "1") (pinfunction "1_1") (pintype "passive"))
      (node (ref "R42") (pin "1") (pinfunction "1_1") (pintype "passive"))
      (node (ref "U12") (pin "21") (pinfunction "T4IN_21") (pintype "input"))
    )
    (net (code "39") (name "Net-(D8-K3)") (class "Default")
      (node (ref "D8") (pin "4") (pinfunction "K3_4") (pintype "passive"))
      (node (ref "J20") (pin "1") (pinfunction "1_1") (pintype "passive"))
      (node (ref "R43") (pin "1") (pinfunction "1_1") (pintype "passive"))
      (node (ref "U12") (pin "17") (pinfunction "R4OUT_17") (pintype "output"))
    )
    (net (code "40") (name "Net-(D10-A)") (class "Default")
      (node (ref "C27") (pin "2") (pinfunction "2_2") (pintype "passive"))
      (node (ref "D10") (pin "1") (pinfunction "A_1") (pintype "passive"))
      (node (ref "D9") (pin "2") (pinfunction "K_2") (pintype "passive"))
      (node (ref "Teensy") (pin "Vin") (pinfunction "Vin_Vin") (pintype "passive"))
    )
    (net (code "41") (name "Net-(D10-K)") (class "Default")
      (node (ref "D10") (pin "2") (pinfunction "K_2") (pintype "passive"))
      (node (ref "D3") (pin "2") (pinfunction "K_2") (pintype "passive"))
      (node (ref "D4") (pin "2") (pinfunction "K_2") (pintype "passive"))
      (node (ref "J18") (pin "1") (pinfunction "1_1") (pintype "passive"))
    )
    (net (code "42") (name "Net-(D11-A)") (class "Default")
      (node (ref "D11") (pin "1") (pinfunction "A_1") (pintype "passive"))
      (node (ref "Teensy") (pin "21") (pinfunction "21/A7_21") (pintype "passive"))
    )
    (net (code "43") (name "Net-(D11-K)") (class "Default")
      (node (ref "D11") (pin "2") (pinfunction "K_2") (pintype "passive"))
      (node (ref "R39") (pin "2") (pinfunction "2_2") (pintype "passive"))
    )
    (net (code "44") (name "Net-(D12-A)") (class "Default")
      (node (ref "D12") (pin "1") (pinfunction "A_1") (pintype "passive"))
      (node (ref "Teensy") (pin "20") (pinfunction "20/A6_20") (pintype "passive"))
    )
    (net (code "45") (name "Net-(D12-K)") (class "Default")
      (node (ref "D12") (pin "2") (pinfunction "K_2") (pintype "passive"))
      (node (ref "R40") (pin "2") (pinfunction "2_2") (pintype "passive"))
    )
    (net (code "46") (name "Net-(D13-A)") (class "Default")
      (node (ref "D13") (pin "1") (pinfunction "A_1") (pintype "passive"))
      (node (ref "Teensy") (pin "19") (pinfunction "19/A5_19") (pintype "passive"))
    )
    (net (code "47") (name "Net-(D13-K)") (class "Default")
      (node (ref "D13") (pin "2") (pinfunction "K_2") (pintype "passive"))
      (node (ref "R41") (pin "2") (pinfunction "2_2") (pintype "passive"))
    )
    (net (code "48") (name "Net-(Teensy-16{slash}A2)") (class "Default")
      (node (ref "R47") (pin "2") (pinfunction "2_2") (pintype "passive"))
      (node (ref "Teensy") (pin "16") (pinfunction "16/A2_16") (pintype "passive"))
      (node (ref "U11") (pin "8") (pinfunction "~{RST}_8") (pintype "passive"))
    )
    (net (code "49") (name "Net-(Teensy-17{slash}A3)") (class "Default")
      (node (ref "R44") (pin "1") (pinfunction "1_1") (pintype "passive"))
      (node (ref "Teensy") (pin "17") (pinfunction "17/A3_17") (pintype "passive"))
      (node (ref "U11") (pin "7") (pinfunction "~{IRQ}_7") (pintype "passive"))
    )
    (net (code "50") (name "Net-(Teensy-G)") (class "Default")
      (node (ref "*") (pin "9") (pinfunction "GND_9") (pintype "passive"))
      (node (ref "Teensy") (pin "GND_4") (pinfunction "G_GND_4") (pintype "passive"))
    )
    (net (code "51") (name "Net-(U7-RXD_ECI)") (class "Default")
      (node (ref "J21") (pin "3") (pinfunction "3_3") (pintype "passive"))
      (node (ref "U7") (pin "12") (pinfunction "RXD_ECI_12") (pintype "passive"))
    )
    (net (code "52") (name "Net-(U7-RXD_SCI)") (class "Default")
      (node (ref "J19") (pin "3") (pinfunction "3_3") (pintype "passive"))
      (node (ref "U7") (pin "20") (pinfunction "RXD_SCI_20") (pintype "passive"))
    )
    (net (code "53") (name "Net-(U7-TXD_ECI)") (class "Default")
      (node (ref "J22") (pin "3") (pinfunction "3_3") (pintype "passive"))
      (node (ref "U7") (pin "13") (pinfunction "TXD_ECI_13") (pintype "passive"))
    )
    (net (code "54") (name "Net-(U7-TXD_SCI)") (class "Default")
      (node (ref "J20") (pin "3") (pinfunction "3_3") (pintype "passive"))
      (node (ref "U7") (pin "21") (pinfunction "TXD_SCI_21") (pintype "passive"))
    )
    (net (code "55") (name "Net-(U7-VBUS)") (class "Default")
      (node (ref "R29") (pin "2") (pinfunction "2_2") (pintype "passive"))
      (node (ref "R30") (pin "2") (pinfunction "2_2") (pintype "passive"))
      (node (ref "U7") (pin "8") (pinfunction "VBUS_8") (pintype "passive"))
    )
    (net (code "56") (name "Net-(U7-~{SUSP}{slash}RI_ECI)") (class "Default")
      (node (ref "R34") (pin "2") (pinfunction "2_2") (pintype "passive"))
      (node (ref "U7") (pin "17") (pinfunction "~{SUSP}/RI_ECI_17") (pintype "passive"))
    )
    (net (code "57") (name "Net-(U7-~{SUSP}{slash}RI_SCI)") (class "Default")
      (node (ref "R33") (pin "1") (pinfunction "1_1") (pintype "passive"))
      (node (ref "U7") (pin "1") (pinfunction "~{SUSP}/RI_SCI_1") (pintype "passive"))
    )
    (net (code "58") (name "Net-(U8-RXD_ECI)") (class "Default")
      (node (ref "J27") (pin "3") (pinfunction "3_3") (pintype "passive"))
      (node (ref "U8") (pin "12") (pinfunction "RXD_ECI_12") (pintype "passive"))
    )
    (net (code "59") (name "Net-(U8-RXD_SCI)") (class "Default")
      (node (ref "J24") (pin "3") (pinfunction "3_3") (pintype "passive"))
      (node (ref "U8") (pin "20") (pinfunction "RXD_SCI_20") (pintype "passive"))
    )
    (net (code "60") (name "Net-(U8-TXD_ECI)") (class "Default")
      (node (ref "J1") (pin "3") (pinfunction "3_3") (pintype "passive"))
      (node (ref "U8") (pin "13") (pinfunction "TXD_ECI_13") (pintype "passive"))
    )
    (net (code "61") (name "Net-(U8-TXD_SCI)") (class "Default")
      (node (ref "J26") (pin "3") (pinfunction "3_3") (pintype "passive"))
      (node (ref "U8") (pin "21") (pinfunction "TXD_SCI_21") (pintype "passive"))
    )
    (net (code "62") (name "Net-(U8-VBUS)") (class "Default")
      (node (ref "R31") (pin "2") (pinfunction "2_2") (pintype "passive"))
      (node (ref "R32") (pin "2") (pinfunction "2_2") (pintype "passive"))
      (node (ref "U8") (pin "8") (pinfunction "VBUS_8") (pintype "passive"))
    )
    (net (code "63") (name "Net-(U8-~{SUSP}{slash}RI_ECI)") (class "Default")
      (node (ref "R36") (pin "2") (pinfunction "2_2") (pintype "passive"))
      (node (ref "U8") (pin "17") (pinfunction "~{SUSP}/RI_ECI_17") (pintype "passive"))
    )
    (net (code "64") (name "Net-(U8-~{SUSP}{slash}RI_SCI)") (class "Default")
      (node (ref "R35") (pin "1") (pinfunction "1_1") (pintype "passive"))
      (node (ref "U8") (pin "1") (pinfunction "~{SUSP}/RI_SCI_1") (pintype "passive"))
    )
    (net (code "65") (name "Net-(U9-RX0)") (class "Default")
      (node (ref "J1") (pin "2") (pinfunction "2_2") (pintype "passive"))
      (node (ref "U9") (pin "17") (pinfunction "RX0_17") (pintype "passive"))
    )
    (net (code "66") (name "Net-(U9-RX1)") (class "Default")
      (node (ref "J26") (pin "2") (pinfunction "2_2") (pintype "passive"))
      (node (ref "U9") (pin "25") (pinfunction "RX1_25") (pintype "passive"))
    )
    (net (code "67") (name "Net-(U9-RX2)") (class "Default")
      (node (ref "J22") (pin "2") (pinfunction "2_2") (pintype "passive"))
      (node (ref "U9") (pin "33") (pinfunction "RX2_33") (pintype "passive"))
    )
    (net (code "68") (name "Net-(U9-RX3)") (class "Default")
      (node (ref "J20") (pin "2") (pinfunction "2_2") (pintype "passive"))
      (node (ref "U9") (pin "41") (pinfunction "RX3_41") (pintype "passive"))
    )
    (net (code "69") (name "Net-(U9-TX0)") (class "Default")
      (node (ref "J27") (pin "2") (pinfunction "2_2") (pintype "passive"))
      (node (ref "U9") (pin "18") (pinfunction "TX0_18") (pintype "passive"))
    )
    (net (code "70") (name "Net-(U9-TX1)") (class "Default")
      (node (ref "J24") (pin "2") (pinfunction "2_2") (pintype "passive"))
      (node (ref "U9") (pin "26") (pinfunction "TX1_26") (pintype "passive"))
    )
    (net (code "71") (name "Net-(U9-TX2)") (class "Default")
      (node (ref "J21") (pin "2") (pinfunction "2_2") (pintype "passive"))
      (node (ref "U9") (pin "34") (pinfunction "TX2_34") (pintype "passive"))
    )
    (net (code "72") (name "Net-(U9-TX3)") (class "Default")
      (node (ref "J19") (pin "2") (pinfunction "2_2") (pintype "passive"))
      (node (ref "U9") (pin "42") (pinfunction "TX3_42") (pintype "passive"))
    )
    (net (code "73") (name "Net-(U9-V_18)") (class "Default")
      (node (ref "C10") (pin "2") (pinfunction "2_2") (pintype "passive"))
      (node (ref "U9") (pin "48") (pinfunction "V_18_48") (pintype "passive"))
    )
    (net (code "74") (name "Net-(U9-XIN)") (class "Default")
      (node (ref "U9") (pin "45") (pinfunction "XIN_45") (pintype "passive"))
      (node (ref "Y3") (pin "1") (pinfunction "1_1") (pintype "passive"))
    )
    (net (code "75") (name "Net-(U9-XOUT)") (class "Default")
      (node (ref "U9") (pin "44") (pinfunction "XOUT_44") (pintype "passive"))
      (node (ref "Y3") (pin "2") (pinfunction "2_2") (pintype "passive"))
    )
    (net (code "76") (name "Net-(U9-~{IRQ})") (class "Default")
      (node (ref "R38") (pin "2") (pinfunction "2_2") (pintype "passive"))
      (node (ref "Teensy") (pin "8") (pinfunction "8_8") (pintype "passive"))
      (node (ref "U9") (pin "7") (pinfunction "~{IRQ}_7") (pintype "passive"))
    )
    (net (code "77") (name "Net-(U9-~{RST})") (class "Default")
      (node (ref "R37") (pin "1") (pinfunction "1_1") (pintype "passive"))
      (node (ref "Teensy") (pin "7") (pinfunction "7_7") (pintype "passive"))
      (node (ref "U9") (pin "8") (pinfunction "~{RST}_8") (pintype "passive"))
    )
    (net (code "78") (name "Net-(U10-C1+)") (class "Default")
      (node (ref "C5") (pin "2") (pinfunction "2_2") (pintype "passive"))
      (node (ref "U10") (pin "10") (pinfunction "C1+_10") (pintype "passive"))
    )
    (net (code "79") (name "Net-(U10-C1-)") (class "Default")
      (node (ref "C5") (pin "1") (pinfunction "1_1") (pintype "passive"))
      (node (ref "U10") (pin "12") (pinfunction "C1-_12") (pintype "passive"))
    )
    (net (code "80") (name "Net-(U10-C2+)") (class "Default")
      (node (ref "C6") (pin "2") (pinfunction "2_2") (pintype "passive"))
      (node (ref "U10") (pin "13") (pinfunction "C2+_13") (pintype "passive"))
    )
    (net (code "81") (name "Net-(U10-C2-)") (class "Default")
      (node (ref "C6") (pin "1") (pinfunction "1_1") (pintype "passive"))
      (node (ref "U10") (pin "14") (pinfunction "C2-_14") (pintype "passive"))
    )
    (net (code "82") (name "Net-(U10-R1IN)") (class "Default")
      (node (ref "J23") (pin "3") (pinfunction "3_3") (pintype "passive"))
      (node (ref "U10") (pin "7") (pinfunction "R1IN_7") (pintype "input"))
    )
    (net (code "83") (name "Net-(U10-R1OUT)") (class "Default")
      (node (ref "U10") (pin "6") (pinfunction "R1OUT_6") (pintype "output"))
      (node (ref "U11") (pin "17") (pinfunction "RX0_17") (pintype "passive"))
    )
    (net (code "84") (name "Net-(U10-R2IN)") (class "Default")
      (node (ref "J25") (pin "3") (pinfunction "3_3") (pintype "passive"))
      (node (ref "U10") (pin "3") (pinfunction "R2IN_3") (pintype "input"))
    )
    (net (code "85") (name "Net-(U10-R2OUT)") (class "Default")
      (node (ref "U10") (pin "4") (pinfunction "R2OUT_4") (pintype "output"))
      (node (ref "U11") (pin "25") (pinfunction "RX1_25") (pintype "passive"))
    )
    (net (code "86") (name "Net-(U10-R3IN)") (class "Default")
      (node (ref "J28") (pin "3") (pinfunction "3_3") (pintype "passive"))
      (node (ref "U10") (pin "23") (pinfunction "R3IN_23") (pintype "input"))
    )
    (net (code "87") (name "Net-(U10-R3OUT)") (class "Default")
      (node (ref "U10") (pin "22") (pinfunction "R3OUT_22") (pintype "output"))
      (node (ref "U11") (pin "33") (pinfunction "RX2_33") (pintype "passive"))
    )
    (net (code "88") (name "Net-(U10-R4IN)") (class "Default")
      (node (ref "J30") (pin "3") (pinfunction "3_3") (pintype "passive"))
      (node (ref "U10") (pin "16") (pinfunction "R4IN_16") (pintype "input"))
    )
    (net (code "89") (name "Net-(U10-R4OUT)") (class "Default")
      (node (ref "U10") (pin "17") (pinfunction "R4OUT_17") (pintype "output"))
      (node (ref "U11") (pin "41") (pinfunction "RX3_41") (pintype "passive"))
    )
    (net (code "90") (name "Net-(U10-T1IN)") (class "Default")
      (node (ref "U10") (pin "5") (pinfunction "T1IN_5") (pintype "input"))
      (node (ref "U11") (pin "18") (pinfunction "TX0_18") (pintype "passive"))
    )
    (net (code "91") (name "Net-(U10-T1OUT)") (class "Default")
      (node (ref "J23") (pin "1") (pinfunction "1_1") (pintype "passive"))
      (node (ref "U10") (pin "2") (pinfunction "T1OUT_2") (pintype "output"))
    )
    (net (code "92") (name "Net-(U10-T2IN)") (class "Default")
      (node (ref "U10") (pin "18") (pinfunction "T2IN_18") (pintype "input"))
      (node (ref "U11") (pin "26") (pinfunction "TX1_26") (pintype "passive"))
    )
    (net (code "93") (name "Net-(U10-T2OUT)") (class "Default")
      (node (ref "J25") (pin "1") (pinfunction "1_1") (pintype "passive"))
      (node (ref "U10") (pin "1") (pinfunction "T2OUT_1") (pintype "output"))
    )
    (net (code "94") (name "Net-(U10-T3IN)") (class "Default")
      (node (ref "U10") (pin "19") (pinfunction "T3IN_19") (pintype "input"))
      (node (ref "U11") (pin "34") (pinfunction "TX2_34") (pintype "passive"))
    )
    (net (code "95") (name "Net-(U10-T3OUT)") (class "Default")
      (node (ref "J28") (pin "1") (pinfunction "1_1") (pintype "passive"))
      (node (ref "U10") (pin "24") (pinfunction "T3OUT_24") (pintype "output"))
    )
    (net (code "96") (name "Net-(U10-T4IN)") (class "Default")
      (node (ref "U10") (pin "21") (pinfunction "T4IN_21") (pintype "input"))
      (node (ref "U11") (pin "42") (pinfunction "TX3_42") (pintype "passive"))
    )
    (net (code "97") (name "Net-(U10-T4OUT)") (class "Default")
      (node (ref "J30") (pin "1") (pinfunction "1_1") (pintype "passive"))
      (node (ref "U10") (pin "20") (pinfunction "T4OUT_20") (pintype "output"))
    )
    (net (code "98") (name "Net-(U10-V+)") (class "Default")
      (node (ref "C8") (pin "2") (pinfunction "2_2") (pintype "passive"))
      (node (ref "U10") (pin "11") (pinfunction "V+_11") (pintype "passive"))
    )
    (net (code "99") (name "Net-(U10-V-)") (class "Default")
      (node (ref "C9") (pin "2") (pinfunction "2_2") (pintype "passive"))
      (node (ref "U10") (pin "15") (pinfunction "V-_15") (pintype "passive"))
    )
    (net (code "100") (name "Net-(U11-V_18)") (class "Default")
      (node (ref "C4") (pin "2") (pinfunction "2_2") (pintype "passive"))
      (node (ref "U11") (pin "48") (pinfunction "V_18_48") (pintype "passive"))
    )
    (net (code "101") (name "Net-(U11-XIN)") (class "Default")
      (node (ref "U11") (pin "45") (pinfunction "XIN_45") (pintype "passive"))
      (node (ref "Y4") (pin "2") (pinfunction "2_2") (pintype "passive"))
    )
    (net (code "102") (name "Net-(U11-XOUT)") (class "Default")
      (node (ref "U11") (pin "44") (pinfunction "XOUT_44") (pintype "passive"))
      (node (ref "Y4") (pin "1") (pinfunction "1_1") (pintype "passive"))
    )
    (net (code "103") (name "Net-(U12-C1+)") (class "Default")
      (node (ref "C14") (pin "2") (pinfunction "2_2") (pintype "passive"))
      (node (ref "U12") (pin "10") (pinfunction "C1+_10") (pintype "passive"))
    )
    (net (code "104") (name "Net-(U12-C1-)") (class "Default")
      (node (ref "C14") (pin "1") (pinfunction "1_1") (pintype "passive"))
      (node (ref "U12") (pin "12") (pinfunction "C1-_12") (pintype "passive"))
    )
    (net (code "105") (name "Net-(U12-C2+)") (class "Default")
      (node (ref "C15") (pin "2") (pinfunction "2_2") (pintype "passive"))
      (node (ref "U12") (pin "13") (pinfunction "C2+_13") (pintype "passive"))
    )
    (net (code "106") (name "Net-(U12-C2-)") (class "Default")
      (node (ref "C15") (pin "1") (pinfunction "1_1") (pintype "passive"))
      (node (ref "U12") (pin "14") (pinfunction "C2-_14") (pintype "passive"))
    )
    (net (code "107") (name "Net-(U12-R1IN)") (class "Default")
      (node (ref "J33") (pin "3") (pinfunction "3_3") (pintype "passive"))
      (node (ref "R51") (pin "2") (pinfunction "2_2") (pintype "passive"))
      (node (ref "U12") (pin "7") (pinfunction "R1IN_7") (pintype "input"))
    )
    (net (code "108") (name "Net-(U12-R2IN)") (class "Default")
      (node (ref "J32") (pin "3") (pinfunction "3_3") (pintype "passive"))
      (node (ref "R49") (pin "2") (pinfunction "2_2") (pintype "passive"))
      (node (ref "U12") (pin "3") (pinfunction "R2IN_3") (pintype "input"))
    )
    (net (code "109") (name "Net-(U12-R3IN)") (class "Default")
      (node (ref "J31") (pin "3") (pinfunction "3_3") (pintype "passive"))
      (node (ref "R46") (pin "2") (pinfunction "2_2") (pintype "passive"))
      (node (ref "U12") (pin "23") (pinfunction "R3IN_23") (pintype "input"))
    )
    (net (code "110") (name "Net-(U12-R4IN)") (class "Default")
      (node (ref "J29") (pin "3") (pinfunction "3_3") (pintype "passive"))
      (node (ref "R43") (pin "2") (pinfunction "2_2") (pintype "passive"))
      (node (ref "U12") (pin "16") (pinfunction "R4IN_16") (pintype "input"))
    )
    (net (code "111") (name "Net-(U12-T1OUT)") (class "Default")
      (node (ref "J33") (pin "1") (pinfunction "1_1") (pintype "passive"))
      (node (ref "R50") (pin "2") (pinfunction "2_2") (pintype "passive"))
      (node (ref "U12") (pin "2") (pinfunction "T1OUT_2") (pintype "output"))
    )
    (net (code "112") (name "Net-(U12-T2OUT)") (class "Default")
      (node (ref "J32") (pin "1") (pinfunction "1_1") (pintype "passive"))
      (node (ref "R48") (pin "2") (pinfunction "2_2") (pintype "passive"))
      (node (ref "U12") (pin "1") (pinfunction "T2OUT_1") (pintype "output"))
    )
    (net (code "113") (name "Net-(U12-T3OUT)") (class "Default")
      (node (ref "J31") (pin "1") (pinfunction "1_1") (pintype "passive"))
      (node (ref "R45") (pin "2") (pinfunction "2_2") (pintype "passive"))
      (node (ref "U12") (pin "24") (pinfunction "T3OUT_24") (pintype "output"))
    )
    (net (code "114") (name "Net-(U12-T4OUT)") (class "Default")
      (node (ref "J29") (pin "1") (pinfunction "1_1") (pintype "passive"))
      (node (ref "R42") (pin "2") (pinfunction "2_2") (pintype "passive"))
      (node (ref "U12") (pin "20") (pinfunction "T4OUT_20") (pintype "output"))
    )
    (net (code "115") (name "Net-(U12-V+)") (class "Default")
      (node (ref "C17") (pin "2") (pinfunction "2_2") (pintype "passive"))
      (node (ref "U12") (pin "11") (pinfunction "V+_11") (pintype "passive"))
    )
    (net (code "116") (name "Net-(U12-V-)") (class "Default")
      (node (ref "C18") (pin "2") (pinfunction "2_2") (pintype "passive"))
      (node (ref "U12") (pin "15") (pinfunction "V-_15") (pintype "passive"))
    )
    (net (code "117") (name "Net-(U12-VCC)") (class "Default")
      (node (ref "C16") (pin "1") (pinfunction "1_1") (pintype "passive"))
      (node (ref "C17") (pin "1") (pinfunction "1_1") (pintype "passive"))
      (node (ref "R53") (pin "1") (pinfunction "1_1") (pintype "passive"))
      (node (ref "U12") (pin "9") (pinfunction "VCC_9") (pintype "passive"))
    )
    (net (code "118") (name "Net-(X5-Shield)") (class "Default")
      (node (ref "L6") (pin "1") (pinfunction "1_1") (pintype "passive"))
      (node (ref "X5") (pin "0") (pinfunction "Shield_0") (pintype "passive"))
    )
    (net (code "119") (name "Net-(X6-Shield)") (class "Default")
      (node (ref "L7") (pin "1") (pinfunction "1_1") (pintype "passive"))
      (node (ref "X6") (pin "0") (pinfunction "Shield_0") (pintype "passive"))
    )
    (net (code "120") (name "V_U1") (class "Default")
      (node (ref "C21") (pin "2") (pinfunction "2_2") (pintype "passive"))
      (node (ref "D4") (pin "1") (pinfunction "A_1") (pintype "passive"))
      (node (ref "L8") (pin "2") (pinfunction "2_2") (pintype "passive"))
      (node (ref "R29") (pin "1") (pinfunction "1_1") (pintype "passive"))
    )
    (net (code "121") (name "V_U2") (class "Default")
      (node (ref "C24") (pin "2") (pinfunction "2_2") (pintype "passive"))
      (node (ref "D3") (pin "1") (pinfunction "A_1") (pintype "passive"))
      (node (ref "L9") (pin "2") (pinfunction "2_2") (pintype "passive"))
      (node (ref "R31") (pin "1") (pinfunction "1_1") (pintype "passive"))
    )
    (net (code "122") (name "unconnected-(*-GND-Pad5)") (class "Default")
      (node (ref "*") (pin "5") (pinfunction "GND_5") (pintype "passive+no_connect"))
    )
    (net (code "123") (name "unconnected-(*-NC-Pad3)") (class "Default")
      (node (ref "*") (pin "3") (pinfunction "NC_3") (pintype "passive+no_connect"))
    )
    (net (code "124") (name "unconnected-(*-NC-Pad8)") (class "Default")
      (node (ref "*") (pin "8") (pinfunction "NC_8") (pintype "passive+no_connect"))
    )
    (net (code "125") (name "unconnected-(*-SWO-Pad6)") (class "Default")
      (node (ref "*") (pin "6") (pinfunction "SWO_6") (pintype "passive+no_connect"))
    )
    (net (code "126") (name "unconnected-(D5-K1-Pad2)") (class "Default")
      (node (ref "D5") (pin "2") (pinfunction "K1_2") (pintype "passive"))
    )
    (net (code "127") (name "unconnected-(D5-K3-Pad4)") (class "Default")
      (node (ref "D5") (pin "4") (pinfunction "K3_4") (pintype "passive"))
    )
    (net (code "128") (name "unconnected-(D8-K2-Pad3)") (class "Default")
      (node (ref "D8") (pin "3") (pinfunction "K2_3") (pintype "passive"))
    )
    (net (code "129") (name "unconnected-(Teensy-5V-Pad5V_USB)") (class "Default")
      (node (ref "Teensy") (pin "5V_USB") (pinfunction "5V_5V_USB") (pintype "passive+no_connect"))
    )
    (net (code "130") (name "unconnected-(Teensy-14{slash}A0-Pad14)") (class "Default")
      (node (ref "Teensy") (pin "14") (pinfunction "14/A0_14") (pintype "passive+no_connect"))
    )
    (net (code "131") (name "unconnected-(Teensy-15{slash}A1-Pad15)") (class "Default")
      (node (ref "Teensy") (pin "15") (pinfunction "15/A1_15") (pintype "passive"))
    )
    (net (code "132") (name "unconnected-(Teensy-18{slash}A4-Pad18)") (class "Default")
      (node (ref "Teensy") (pin "18") (pinfunction "18/A4_18") (pintype "passive+no_connect"))
    )
    (net (code "133") (name "unconnected-(Teensy-22{slash}A8-Pad22)") (class "Default")
      (node (ref "Teensy") (pin "22") (pinfunction "22/A8_22") (pintype "passive+no_connect"))
    )
    (net (code "134") (name "unconnected-(Teensy-23{slash}A9-Pad23)") (class "Default")
      (node (ref "Teensy") (pin "23") (pinfunction "23/A9_23") (pintype "passive+no_connect"))
    )
    (net (code "135") (name "unconnected-(Teensy-31{slash}A12-Pad31)") (class "Default")
      (node (ref "Teensy") (pin "31") (pinfunction "31/A12_31") (pintype "passive+no_connect"))
    )
    (net (code "136") (name "unconnected-(Teensy-32{slash}A13-Pad32)") (class "Default")
      (node (ref "Teensy") (pin "32") (pinfunction "32/A13_32") (pintype "passive+no_connect"))
    )
    (net (code "137") (name "unconnected-(Teensy-33{slash}A14-Pad33)") (class "Default")
      (node (ref "Teensy") (pin "33") (pinfunction "33/A14_33") (pintype "passive+no_connect"))
    )
    (net (code "138") (name "unconnected-(Teensy-34{slash}A15-Pad34)") (class "Default")
      (node (ref "Teensy") (pin "34") (pinfunction "34/A15_34") (pintype "passive+no_connect"))
    )
    (net (code "139") (name "unconnected-(Teensy-35{slash}A16-Pad35)") (class "Default")
      (node (ref "Teensy") (pin "35") (pinfunction "35/A16_35") (pintype "passive+no_connect"))
    )
    (net (code "140") (name "unconnected-(Teensy-36{slash}A17-Pad36)") (class "Default")
      (node (ref "Teensy") (pin "36") (pinfunction "36/A17_36") (pintype "passive+no_connect"))
    )
    (net (code "141") (name "unconnected-(Teensy-37{slash}A18-Pad37)") (class "Default")
      (node (ref "Teensy") (pin "37") (pinfunction "37/A18_37") (pintype "passive+no_connect"))
    )
    (net (code "142") (name "unconnected-(Teensy-38{slash}A19-Pad38)") (class "Default")
      (node (ref "Teensy") (pin "38") (pinfunction "38/A19_38") (pintype "passive+no_connect"))
    )
    (net (code "143") (name "unconnected-(Teensy-39{slash}A20-Pad39)") (class "Default")
      (node (ref "Teensy") (pin "39") (pinfunction "39/A20_39") (pintype "passive+no_connect"))
    )
    (net (code "144") (name "unconnected-(Teensy-GND-PadGND_3)") (class "Default")
      (node (ref "Teensy") (pin "GND_3") (pinfunction "GND_GND_3") (pintype "passive+no_connect"))
    )
    (net (code "145") (name "unconnected-(Teensy-GND-PadGND_5)") (class "Default")
      (node (ref "Teensy") (pin "GND_5") (pinfunction "GND_GND_5") (pintype "passive+no_connect"))
    )
    (net (code "146") (name "unconnected-(Teensy-GND-PadGND_6)") (class "Default")
      (node (ref "Teensy") (pin "GND_6") (pinfunction "GND_GND_6") (pintype "passive+no_connect"))
    )
    (net (code "147") (name "unconnected-(Teensy-Pad0)") (class "Default")
      (node (ref "Teensy") (pin "0") (pinfunction "0_0") (pintype "passive+no_connect"))
    )
    (net (code "148") (name "unconnected-(Teensy-Pad1)") (class "Default")
      (node (ref "Teensy") (pin "1") (pinfunction "1_1") (pintype "passive+no_connect"))
    )
    (net (code "149") (name "unconnected-(Teensy-Pad2)") (class "Default")
      (node (ref "Teensy") (pin "2") (pinfunction "2_2") (pintype "passive+no_connect"))
    )
    (net (code "150") (name "unconnected-(Teensy-Pad3)") (class "Default")
      (node (ref "Teensy") (pin "3") (pinfunction "3_3") (pintype "passive+no_connect"))
    )
    (net (code "151") (name "unconnected-(Teensy-Pad3.3V)") (class "Default")
      (node (ref "Teensy") (pin "3.3V") (pinfunction "3.3V_3.3V") (pintype "passive+no_connect"))
    )
    (net (code "152") (name "unconnected-(Teensy-Pad4)") (class "Default")
      (node (ref "Teensy") (pin "4") (pinfunction "4_4") (pintype "passive+no_connect"))
    )
    (net (code "153") (name "unconnected-(Teensy-Pad9)") (class "Default")
      (node (ref "Teensy") (pin "9") (pinfunction "9_9") (pintype "passive"))
    )
    (net (code "154") (name "unconnected-(Teensy-Pad12)") (class "Default")
      (node (ref "Teensy") (pin "12") (pinfunction "12_12") (pintype "passive+no_connect"))
    )
    (net (code "155") (name "unconnected-(Teensy-Pad24)") (class "Default")
      (node (ref "Teensy") (pin "24") (pinfunction "24_24") (pintype "passive+no_connect"))
    )
    (net (code "156") (name "unconnected-(Teensy-Pad25)") (class "Default")
      (node (ref "Teensy") (pin "25") (pinfunction "25_25") (pintype "passive+no_connect"))
    )
    (net (code "157") (name "unconnected-(Teensy-Pad26)") (class "Default")
      (node (ref "Teensy") (pin "26") (pinfunction "26_26") (pintype "passive+no_connect"))
    )
    (net (code "158") (name "unconnected-(Teensy-Pad27)") (class "Default")
      (node (ref "Teensy") (pin "27") (pinfunction "27_27") (pintype "passive+no_connect"))
    )
    (net (code "159") (name "unconnected-(Teensy-Pad28)") (class "Default")
      (node (ref "Teensy") (pin "28") (pinfunction "28_28") (pintype "passive+no_connect"))
    )
    (net (code "160") (name "unconnected-(Teensy-Pad29)") (class "Default")
      (node (ref "Teensy") (pin "29") (pinfunction "29_29") (pintype "passive+no_connect"))
    )
    (net (code "161") (name "unconnected-(Teensy-Pad30)") (class "Default")
      (node (ref "Teensy") (pin "30") (pinfunction "30_30") (pintype "passive+no_connect"))
    )
    (net (code "162") (name "unconnected-(Teensy-PadA21)") (class "Default")
      (node (ref "Teensy") (pin "A21") (pinfunction "A21_A21") (pintype "passive+no_connect"))
    )
    (net (code "163") (name "unconnected-(Teensy-PadA22)") (class "Default")
      (node (ref "Teensy") (pin "A22") (pinfunction "A22_A22") (pintype "passive+no_connect"))
    )
    (net (code "164") (name "unconnected-(Teensy-PadAGND)") (class "Default")
      (node (ref "Teensy") (pin "AGND") (pinfunction "AGND_AGND") (pintype "passive+no_connect"))
    )
    (net (code "165") (name "unconnected-(Teensy-PadDM)") (class "Default")
      (node (ref "Teensy") (pin "DM") (pinfunction "DM_DM") (pintype "passive+no_connect"))
    )
    (net (code "166") (name "unconnected-(Teensy-PadDP)") (class "Default")
      (node (ref "Teensy") (pin "DP") (pinfunction "DP_DP") (pintype "passive+no_connect"))
    )
    (net (code "167") (name "unconnected-(Teensy-PadProgram)") (class "Default")
      (node (ref "Teensy") (pin "Program") (pinfunction "Program_Program") (pintype "passive+no_connect"))
    )
    (net (code "168") (name "unconnected-(Teensy-PadVBat)") (class "Default")
      (node (ref "Teensy") (pin "VBat") (pinfunction "VBat_VBat") (pintype "passive+no_connect"))
    )
    (net (code "169") (name "unconnected-(U7-CTS_ECI-Pad10)") (class "Default")
      (node (ref "U7") (pin "10") (pinfunction "CTS_ECI_10") (pintype "passive+no_connect"))
    )
    (net (code "170") (name "unconnected-(U7-CTS_SCI-Pad18)") (class "Default")
      (node (ref "U7") (pin "18") (pinfunction "CTS_SCI_18") (pintype "passive+no_connect"))
    )
    (net (code "171") (name "unconnected-(U7-GPIO0_DCD_SCI-Pad24)") (class "Default")
      (node (ref "U7") (pin "24") (pinfunction "GPIO0_DCD_SCI_24") (pintype "passive+no_connect"))
    )
    (net (code "172") (name "unconnected-(U7-GPIO0_DTR_ECI-Pad15)") (class "Default")
      (node (ref "U7") (pin "15") (pinfunction "GPIO0_DTR_ECI_15") (pintype "passive+no_connect"))
    )
    (net (code "173") (name "unconnected-(U7-GPIO1_DSR_ECI-Pad14)") (class "Default")
      (node (ref "U7") (pin "14") (pinfunction "GPIO1_DSR_ECI_14") (pintype "passive+no_connect"))
    )
    (net (code "174") (name "unconnected-(U7-GPIO1_DTR_SCI-Pad23)") (class "Default")
      (node (ref "U7") (pin "23") (pinfunction "GPIO1_DTR_SCI_23") (pintype "passive+no_connect"))
    )
    (net (code "175") (name "unconnected-(U7-GPIO2_DSR_SCI-Pad22)") (class "Default")
      (node (ref "U7") (pin "22") (pinfunction "GPIO2_DSR_SCI_22") (pintype "passive+no_connect"))
    )
    (net (code "176") (name "unconnected-(U7-NC{slash}DCD_ECI{slash}VPP-Pad16)") (class "Default")
      (node (ref "U7") (pin "16") (pinfunction "NC/DCD_ECI/VPP_16") (pintype "passive+no_connect"))
    )
    (net (code "177") (name "unconnected-(U7-RTS_ECI-Pad11)") (class "Default")
      (node (ref "U7") (pin "11") (pinfunction "RTS_ECI_11") (pintype "passive+no_connect"))
    )
    (net (code "178") (name "unconnected-(U7-RTS_SCI-Pad19)") (class "Default")
      (node (ref "U7") (pin "19") (pinfunction "RTS_SCI_19") (pintype "passive+no_connect"))
    )
    (net (code "179") (name "unconnected-(U8-CTS_ECI-Pad10)") (class "Default")
      (node (ref "U8") (pin "10") (pinfunction "CTS_ECI_10") (pintype "passive+no_connect"))
    )
    (net (code "180") (name "unconnected-(U8-CTS_SCI-Pad18)") (class "Default")
      (node (ref "U8") (pin "18") (pinfunction "CTS_SCI_18") (pintype "passive+no_connect"))
    )
    (net (code "181") (name "unconnected-(U8-GPIO0_DCD_SCI-Pad24)") (class "Default")
      (node (ref "U8") (pin "24") (pinfunction "GPIO0_DCD_SCI_24") (pintype "passive+no_connect"))
    )
    (net (code "182") (name "unconnected-(U8-GPIO0_DTR_ECI-Pad15)") (class "Default")
      (node (ref "U8") (pin "15") (pinfunction "GPIO0_DTR_ECI_15") (pintype "passive+no_connect"))
    )
    (net (code "183") (name "unconnected-(U8-GPIO1_DSR_ECI-Pad14)") (class "Default")
      (node (ref "U8") (pin "14") (pinfunction "GPIO1_DSR_ECI_14") (pintype "passive+no_connect"))
    )
    (net (code "184") (name "unconnected-(U8-GPIO1_DTR_SCI-Pad23)") (class "Default")
      (node (ref "U8") (pin "23") (pinfunction "GPIO1_DTR_SCI_23") (pintype "passive+no_connect"))
    )
    (net (code "185") (name "unconnected-(U8-GPIO2_DSR_SCI-Pad22)") (class "Default")
      (node (ref "U8") (pin "22") (pinfunction "GPIO2_DSR_SCI_22") (pintype "passive+no_connect"))
    )
    (net (code "186") (name "unconnected-(U8-NC{slash}DCD_ECI{slash}VPP-Pad16)") (class "Default")
      (node (ref "U8") (pin "16") (pinfunction "NC/DCD_ECI/VPP_16") (pintype "passive+no_connect"))
    )
    (net (code "187") (name "unconnected-(U8-RTS_ECI-Pad11)") (class "Default")
      (node (ref "U8") (pin "11") (pinfunction "RTS_ECI_11") (pintype "passive+no_connect"))
    )
    (net (code "188") (name "unconnected-(U8-RTS_SCI-Pad19)") (class "Default")
      (node (ref "U8") (pin "19") (pinfunction "RTS_SCI_19") (pintype "passive+no_connect"))
    )
    (net (code "189") (name "unconnected-(U9-GPIO0-Pad11)") (class "Default")
      (node (ref "U9") (pin "11") (pinfunction "GPIO0_11") (pintype "passive+no_connect"))
    )
    (net (code "190") (name "unconnected-(U9-GPIO1-Pad12)") (class "Default")
      (node (ref "U9") (pin "12") (pinfunction "GPIO1_12") (pintype "passive+no_connect"))
    )
    (net (code "191") (name "unconnected-(U9-GPIO2-Pad13)") (class "Default")
      (node (ref "U9") (pin "13") (pinfunction "GPIO2_13") (pintype "passive+no_connect"))
    )
    (net (code "192") (name "unconnected-(U9-GPIO3-Pad14)") (class "Default")
      (node (ref "U9") (pin "14") (pinfunction "GPIO3_14") (pintype "passive+no_connect"))
    )
    (net (code "193") (name "unconnected-(U9-GPIO4-Pad19)") (class "Default")
      (node (ref "U9") (pin "19") (pinfunction "GPIO4_19") (pintype "passive+no_connect"))
    )
    (net (code "194") (name "unconnected-(U9-GPIO5-Pad20)") (class "Default")
      (node (ref "U9") (pin "20") (pinfunction "GPIO5_20") (pintype "passive+no_connect"))
    )
    (net (code "195") (name "unconnected-(U9-GPIO6-Pad21)") (class "Default")
      (node (ref "U9") (pin "21") (pinfunction "GPIO6_21") (pintype "passive+no_connect"))
    )
    (net (code "196") (name "unconnected-(U9-GPIO7-Pad22)") (class "Default")
      (node (ref "U9") (pin "22") (pinfunction "GPIO7_22") (pintype "passive+no_connect"))
    )
    (net (code "197") (name "unconnected-(U9-GPIO8-Pad27)") (class "Default")
      (node (ref "U9") (pin "27") (pinfunction "GPIO8_27") (pintype "passive+no_connect"))
    )
    (net (code "198") (name "unconnected-(U9-GPIO9-Pad28)") (class "Default")
      (node (ref "U9") (pin "28") (pinfunction "GPIO9_28") (pintype "passive+no_connect"))
    )
    (net (code "199") (name "unconnected-(U9-GPIO10-Pad29)") (class "Default")
      (node (ref "U9") (pin "29") (pinfunction "GPIO10_29") (pintype "passive+no_connect"))
    )
    (net (code "200") (name "unconnected-(U9-GPIO11-Pad30)") (class "Default")
      (node (ref "U9") (pin "30") (pinfunction "GPIO11_30") (pintype "passive+no_connect"))
    )
    (net (code "201") (name "unconnected-(U9-GPIO12-Pad35)") (class "Default")
      (node (ref "U9") (pin "35") (pinfunction "GPIO12_35") (pintype "passive+no_connect"))
    )
    (net (code "202") (name "unconnected-(U9-GPIO13-Pad36)") (class "Default")
      (node (ref "U9") (pin "36") (pinfunction "GPIO13_36") (pintype "passive+no_connect"))
    )
    (net (code "203") (name "unconnected-(U9-GPIO14-Pad37)") (class "Default")
      (node (ref "U9") (pin "37") (pinfunction "GPIO14_37") (pintype "passive+no_connect"))
    )
    (net (code "204") (name "unconnected-(U9-GPIO15-Pad38)") (class "Default")
      (node (ref "U9") (pin "38") (pinfunction "GPIO15_38") (pintype "passive+no_connect"))
    )
    (net (code "205") (name "unconnected-(U9-~{RTS0}-Pad15)") (class "Default")
      (node (ref "U9") (pin "15") (pinfunction "~{RTS0}_15") (pintype "passive+no_connect"))
    )
    (net (code "206") (name "unconnected-(U9-~{RTS1}-Pad23)") (class "Default")
      (node (ref "U9") (pin "23") (pinfunction "~{RTS1}_23") (pintype "passive+no_connect"))
    )
    (net (code "207") (name "unconnected-(U9-~{RTS2}-Pad31)") (class "Default")
      (node (ref "U9") (pin "31") (pinfunction "~{RTS2}_31") (pintype "passive+no_connect"))
    )
    (net (code "208") (name "unconnected-(U11-GPIO0-Pad11)") (class "Default")
      (node (ref "U11") (pin "11") (pinfunction "GPIO0_11") (pintype "passive+no_connect"))
    )
    (net (code "209") (name "unconnected-(U11-GPIO1-Pad12)") (class "Default")
      (node (ref "U11") (pin "12") (pinfunction "GPIO1_12") (pintype "passive+no_connect"))
    )
    (net (code "210") (name "unconnected-(U11-GPIO2-Pad13)") (class "Default")
      (node (ref "U11") (pin "13") (pinfunction "GPIO2_13") (pintype "passive+no_connect"))
    )
    (net (code "211") (name "unconnected-(U11-GPIO3-Pad14)") (class "Default")
      (node (ref "U11") (pin "14") (pinfunction "GPIO3_14") (pintype "passive+no_connect"))
    )
    (net (code "212") (name "unconnected-(U11-GPIO4-Pad19)") (class "Default")
      (node (ref "U11") (pin "19") (pinfunction "GPIO4_19") (pintype "passive+no_connect"))
    )
    (net (code "213") (name "unconnected-(U11-GPIO5-Pad20)") (class "Default")
      (node (ref "U11") (pin "20") (pinfunction "GPIO5_20") (pintype "passive+no_connect"))
    )
    (net (code "214") (name "unconnected-(U11-GPIO6-Pad21)") (class "Default")
      (node (ref "U11") (pin "21") (pinfunction "GPIO6_21") (pintype "passive+no_connect"))
    )
    (net (code "215") (name "unconnected-(U11-GPIO7-Pad22)") (class "Default")
      (node (ref "U11") (pin "22") (pinfunction "GPIO7_22") (pintype "passive+no_connect"))
    )
    (net (code "216") (name "unconnected-(U11-GPIO8-Pad27)") (class "Default")
      (node (ref "U11") (pin "27") (pinfunction "GPIO8_27") (pintype "passive+no_connect"))
    )
    (net (code "217") (name "unconnected-(U11-GPIO9-Pad28)") (class "Default")
      (node (ref "U11") (pin "28") (pinfunction "GPIO9_28") (pintype "passive+no_connect"))
    )
    (net (code "218") (name "unconnected-(U11-GPIO10-Pad29)") (class "Default")
      (node (ref "U11") (pin "29") (pinfunction "GPIO10_29") (pintype "passive+no_connect"))
    )
    (net (code "219") (name "unconnected-(U11-GPIO11-Pad30)") (class "Default")
      (node (ref "U11") (pin "30") (pinfunction "GPIO11_30") (pintype "passive+no_connect"))
    )
    (net (code "220") (name "unconnected-(U11-GPIO12-Pad35)") (class "Default")
      (node (ref "U11") (pin "35") (pinfunction "GPIO12_35") (pintype "passive+no_connect"))
    )
    (net (code "221") (name "unconnected-(U11-GPIO13-Pad36)") (class "Default")
      (node (ref "U11") (pin "36") (pinfunction "GPIO13_36") (pintype "passive+no_connect"))
    )
    (net (code "222") (name "unconnected-(U11-GPIO14-Pad37)") (class "Default")
      (node (ref "U11") (pin "37") (pinfunction "GPIO14_37") (pintype "passive+no_connect"))
    )
    (net (code "223") (name "unconnected-(U11-GPIO15-Pad38)") (class "Default")
      (node (ref "U11") (pin "38") (pinfunction "GPIO15_38") (pintype "passive+no_connect"))
    )
    (net (code "224") (name "unconnected-(U11-~{RTS0}-Pad15)") (class "Default")
      (node (ref "U11") (pin "15") (pinfunction "~{RTS0}_15") (pintype "passive"))
    )
    (net (code "225") (name "unconnected-(U11-~{RTS1}-Pad23)") (class "Default")
      (node (ref "U11") (pin "23") (pinfunction "~{RTS1}_23") (pintype "passive"))
    )
    (net (code "226") (name "unconnected-(U11-~{RTS2}-Pad31)") (class "Default")
      (node (ref "U11") (pin "31") (pinfunction "~{RTS2}_31") (pintype "passive+no_connect"))
    )
    (net (code "227") (name "unconnected-(U11-~{RTS3}-Pad39)") (class "Default")
      (node (ref "U11") (pin "39") (pinfunction "~{RTS3}_39") (pintype "passive+no_connect"))
    )
  )
)
